# stm32_v0_7.net
KiCad netlist of a schematic drawn in EAGLE
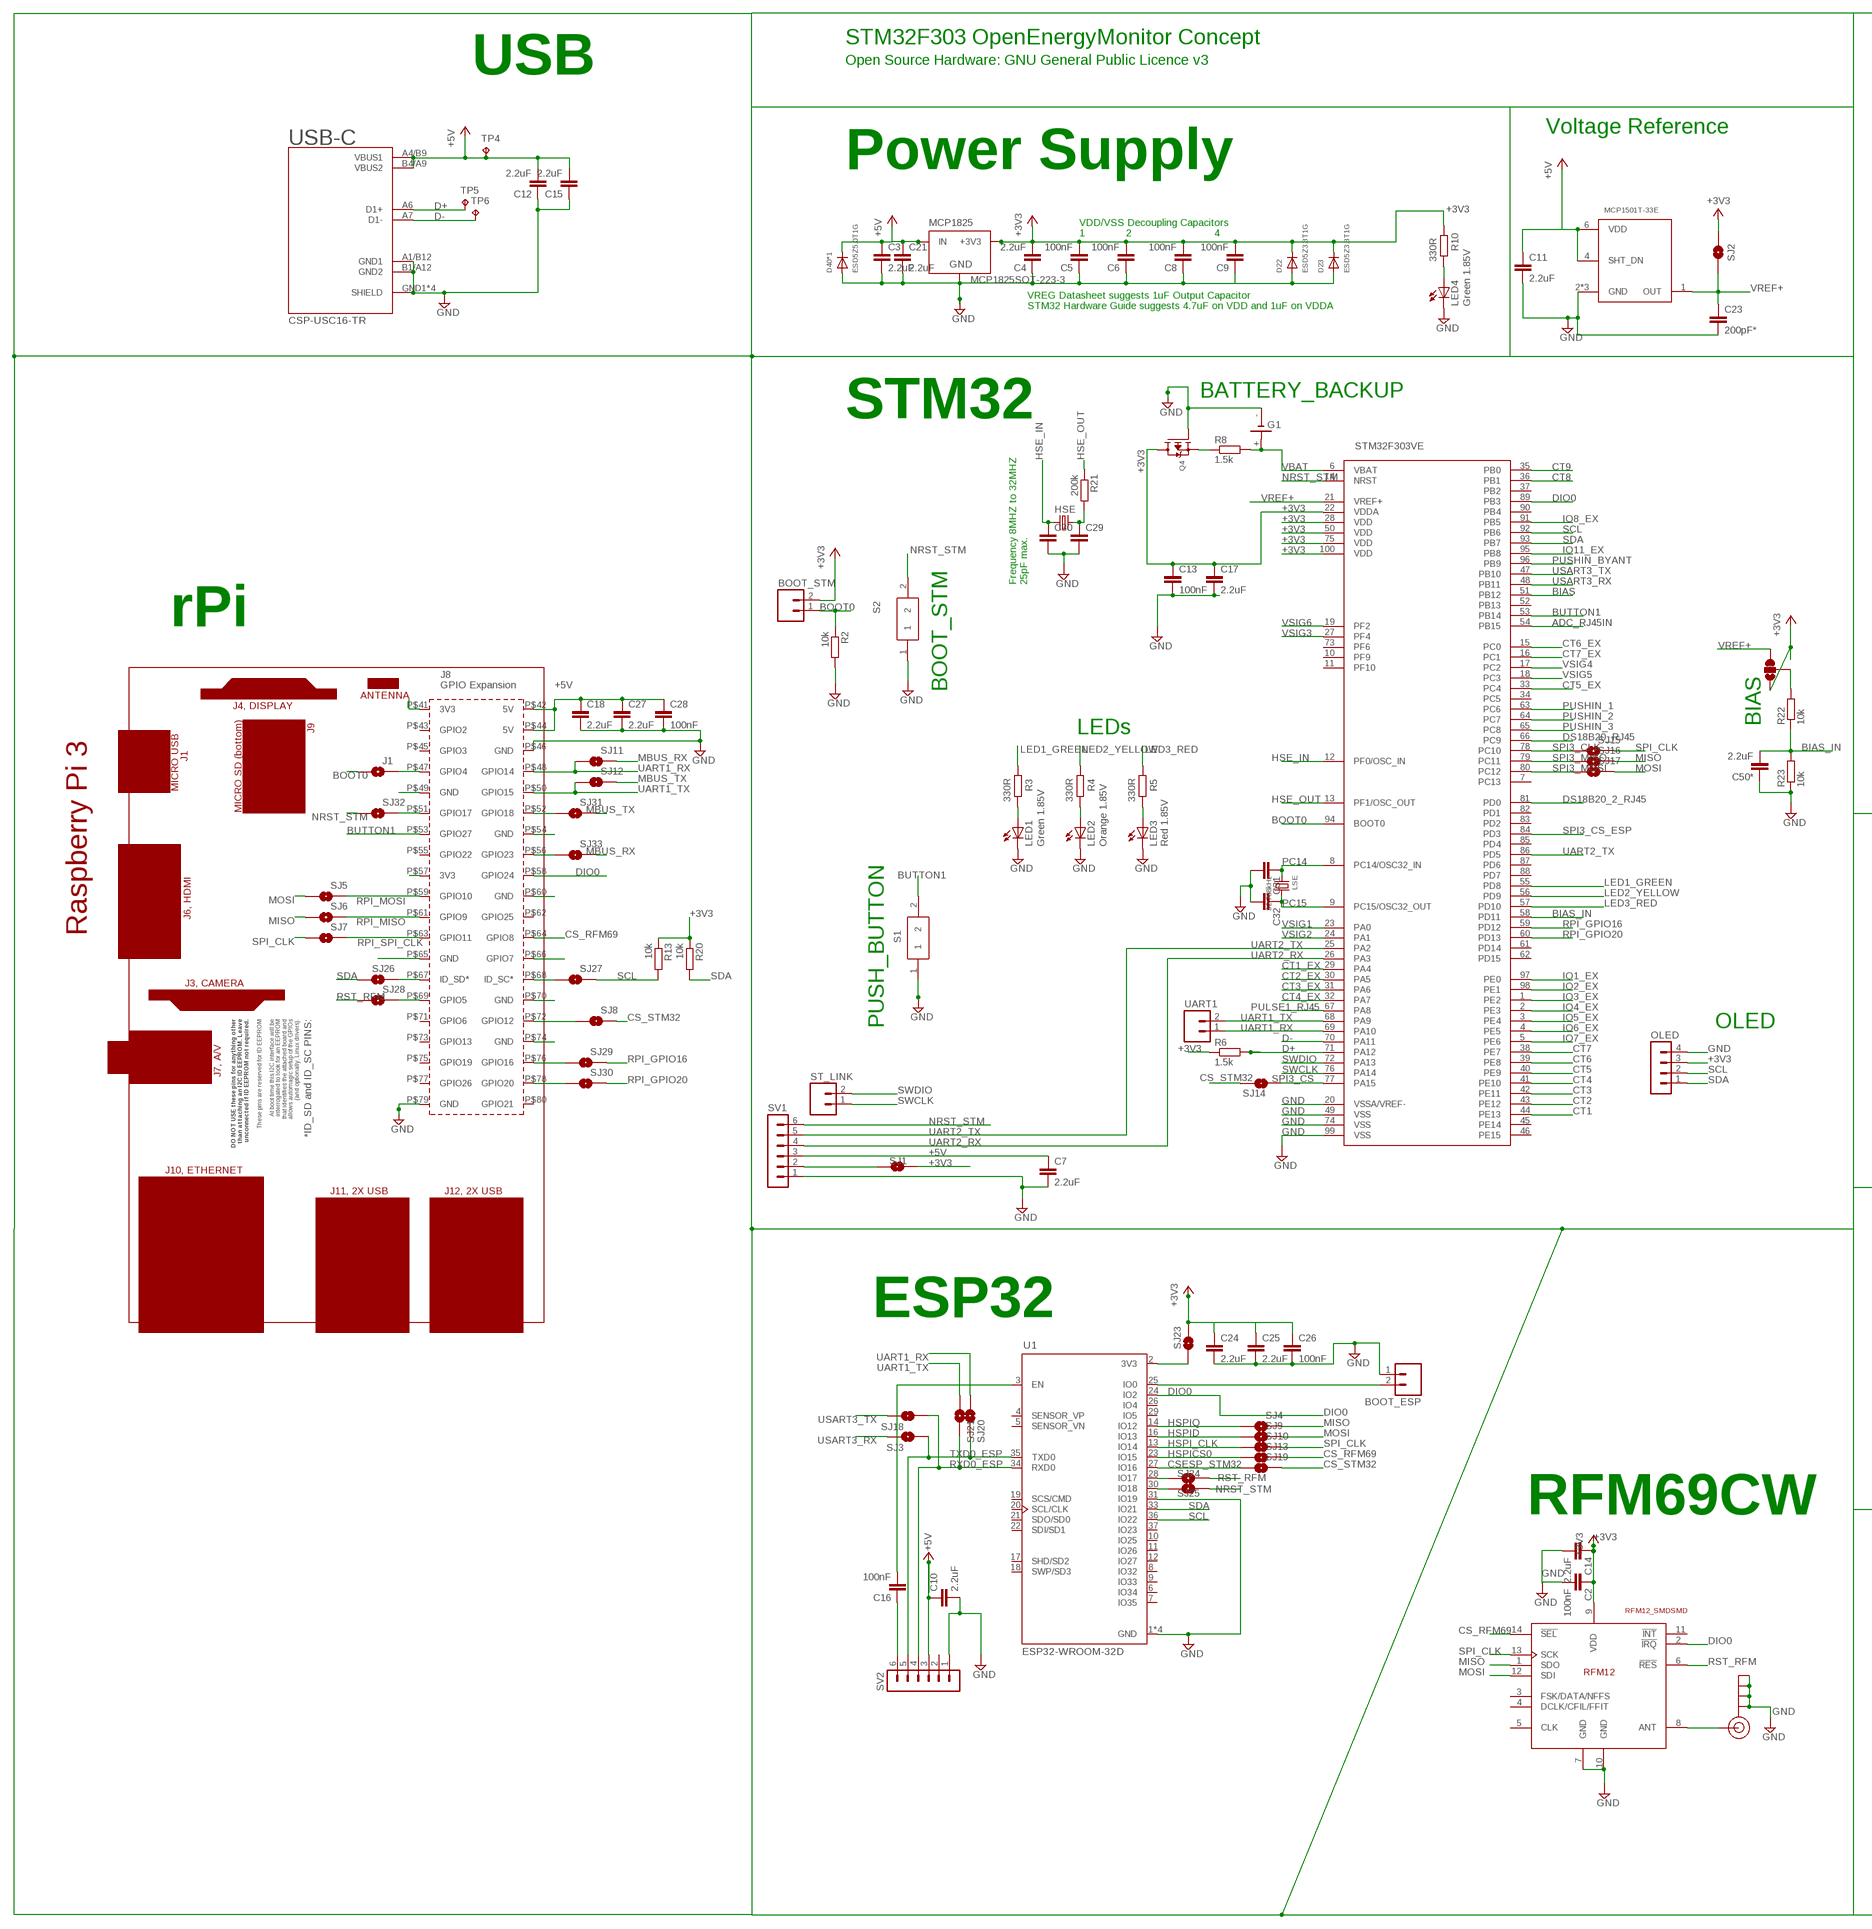
[diagram p0: schematic, sheet 1, part 1 of 2]
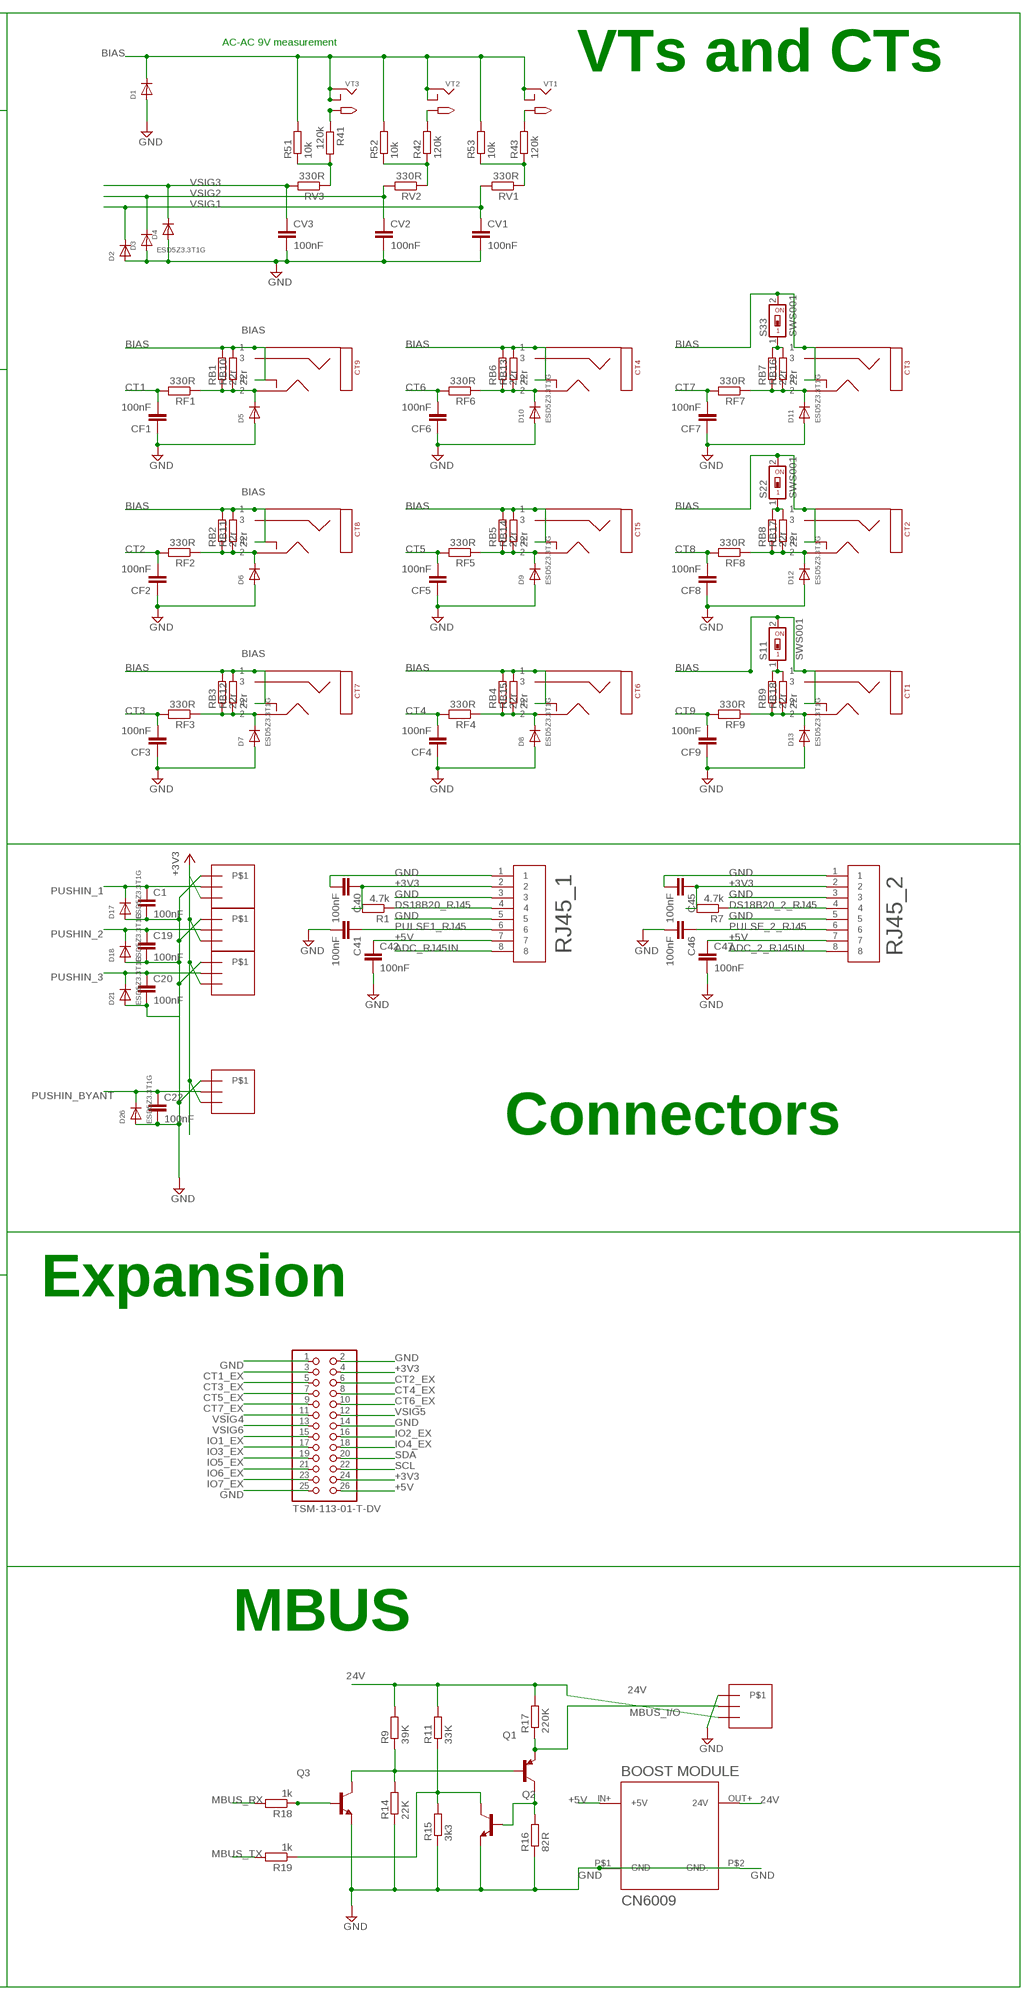
[diagram p1: schematic, sheet 1, part 2 of 2]

(export (version "E")
  (design (tool "Eeschema 10.0.6"))
  (components
    (comp (ref "BOOT_ESP")
      (value "M02PTH")
      (footprint "eagle-import:1X02")
      (libsource (lib "eagle-import") (part "M02PTH"))
    )
    (comp (ref "BOOT_STM")
      (value "M02PTH")
      (footprint "eagle-import:1X02")
      (libsource (lib "eagle-import") (part "M02PTH"))
    )
    (comp (ref "C1")
      (value "100nF")
      (footprint "eagle-import:C0603")
      (libsource (lib "eagle-import") (part "resistor_C-EUC0603"))
    )
    (comp (ref "C2")
      (value "100nF")
      (footprint "eagle-import:C0603")
      (libsource (lib "eagle-import") (part "resistor_C-EUC0603"))
    )
    (comp (ref "C3")
      (value "2.2uF")
      (footprint "eagle-import:C0805")
      (libsource (lib "eagle-import") (part "C-EUC0805"))
    )
    (comp (ref "C4")
      (value "2.2uF")
      (footprint "eagle-import:C0805")
      (libsource (lib "eagle-import") (part "C-EUC0805"))
    )
    (comp (ref "C5")
      (value "100nF")
      (footprint "eagle-import:C0603")
      (libsource (lib "eagle-import") (part "resistor_C-EUC0603"))
    )
    (comp (ref "C6")
      (value "100nF")
      (footprint "eagle-import:C0603")
      (libsource (lib "eagle-import") (part "resistor_C-EUC0603"))
    )
    (comp (ref "C7")
      (value "2.2uF")
      (footprint "eagle-import:C0805")
      (libsource (lib "eagle-import") (part "C-EUC0805"))
    )
    (comp (ref "C8")
      (value "100nF")
      (footprint "eagle-import:C0603")
      (libsource (lib "eagle-import") (part "resistor_C-EUC0603"))
    )
    (comp (ref "C9")
      (value "100nF")
      (footprint "eagle-import:C0603")
      (libsource (lib "eagle-import") (part "resistor_C-EUC0603"))
    )
    (comp (ref "C10")
      (value "2.2uF")
      (footprint "eagle-import:C0805")
      (libsource (lib "eagle-import") (part "C-EUC0805"))
    )
    (comp (ref "C11")
      (value "2.2uF")
      (footprint "eagle-import:C0805")
      (libsource (lib "eagle-import") (part "C-EUC0805"))
    )
    (comp (ref "C12")
      (value "2.2uF")
      (footprint "eagle-import:C0805")
      (libsource (lib "eagle-import") (part "C-EUC0805"))
    )
    (comp (ref "C13")
      (value "100nF")
      (footprint "eagle-import:C0603")
      (libsource (lib "eagle-import") (part "C-EUC0603"))
    )
    (comp (ref "C14")
      (value "2.2uF")
      (footprint "eagle-import:C0805")
      (libsource (lib "eagle-import") (part "C-EUC0805"))
    )
    (comp (ref "C15")
      (value "2.2uF")
      (footprint "eagle-import:C0805")
      (libsource (lib "eagle-import") (part "C-EUC0805"))
    )
    (comp (ref "C16")
      (value "100nF")
      (footprint "eagle-import:C0603")
      (libsource (lib "eagle-import") (part "resistor_C-EUC0603"))
    )
    (comp (ref "C17")
      (value "2.2uF")
      (footprint "eagle-import:C0805")
      (libsource (lib "eagle-import") (part "C-EUC0805"))
    )
    (comp (ref "C18")
      (value "2.2uF")
      (footprint "eagle-import:C0805")
      (libsource (lib "eagle-import") (part "C-EUC0805"))
    )
    (comp (ref "C19")
      (value "100nF")
      (footprint "eagle-import:C0603")
      (libsource (lib "eagle-import") (part "resistor_C-EUC0603"))
    )
    (comp (ref "C20")
      (value "100nF")
      (footprint "eagle-import:C0603")
      (libsource (lib "eagle-import") (part "resistor_C-EUC0603"))
    )
    (comp (ref "C21")
      (value "2.2uF")
      (footprint "eagle-import:C0805")
      (libsource (lib "eagle-import") (part "C-EUC0805"))
    )
    (comp (ref "C22")
      (value "100nF")
      (footprint "eagle-import:C0603")
      (libsource (lib "eagle-import") (part "resistor_C-EUC0603"))
    )
    (comp (ref "C23")
      (value "200pF*")
      (footprint "eagle-import:C0603")
      (libsource (lib "eagle-import") (part "C-EUC0603"))
    )
    (comp (ref "C24")
      (value "2.2uF")
      (footprint "eagle-import:C0805")
      (libsource (lib "eagle-import") (part "C-EUC0805"))
    )
    (comp (ref "C25")
      (value "2.2uF")
      (footprint "eagle-import:C0805")
      (libsource (lib "eagle-import") (part "C-EUC0805"))
    )
    (comp (ref "C26")
      (value "100nF")
      (footprint "eagle-import:C0603")
      (libsource (lib "eagle-import") (part "resistor_C-EUC0603"))
    )
    (comp (ref "C27")
      (value "2.2uF")
      (footprint "eagle-import:C0805")
      (libsource (lib "eagle-import") (part "C-EUC0805"))
    )
    (comp (ref "C28")
      (value "100nF")
      (footprint "eagle-import:C0603")
      (libsource (lib "eagle-import") (part "resistor_C-EUC0603"))
    )
    (comp (ref "C29")
      (value "5nF")
      (footprint "eagle-import:C0603")
      (libsource (lib "eagle-import") (part "C-EUC0603"))
    )
    (comp (ref "C30")
      (value "5nF")
      (footprint "eagle-import:C0603")
      (libsource (lib "eagle-import") (part "C-EUC0603"))
    )
    (comp (ref "C31")
      (value "2.2uF")
      (footprint "eagle-import:C0805")
      (libsource (lib "eagle-import") (part "C-EUC0805"))
    )
    (comp (ref "C32")
      (value "2.2uF")
      (footprint "eagle-import:C0805")
      (libsource (lib "eagle-import") (part "C-EUC0805"))
    )
    (comp (ref "C40")
      (value "100nF")
      (footprint "eagle-import:C0603")
      (libsource (lib "eagle-import") (part "resistor_C-EUC0603"))
    )
    (comp (ref "C41")
      (value "100nF")
      (footprint "eagle-import:C0603")
      (libsource (lib "eagle-import") (part "resistor_C-EUC0603"))
    )
    (comp (ref "C42")
      (value "100nF")
      (footprint "eagle-import:C0603")
      (libsource (lib "eagle-import") (part "resistor_C-EUC0603"))
    )
    (comp (ref "C45")
      (value "100nF")
      (footprint "eagle-import:C0603")
      (libsource (lib "eagle-import") (part "resistor_C-EUC0603"))
    )
    (comp (ref "C46")
      (value "100nF")
      (footprint "eagle-import:C0603")
      (libsource (lib "eagle-import") (part "resistor_C-EUC0603"))
    )
    (comp (ref "C47")
      (value "100nF")
      (footprint "eagle-import:C0603")
      (libsource (lib "eagle-import") (part "resistor_C-EUC0603"))
    )
    (comp (ref "C50*")
      (value "2.2uF")
      (footprint "eagle-import:C0805")
      (libsource (lib "eagle-import") (part "C-EUC0805"))
    )
    (comp (ref "CF1")
      (value "100nF")
      (footprint "eagle-import:C0603")
      (libsource (lib "eagle-import") (part "resistor_C-EUC0603"))
    )
    (comp (ref "CF2")
      (value "100nF")
      (footprint "eagle-import:C0603")
      (libsource (lib "eagle-import") (part "resistor_C-EUC0603"))
    )
    (comp (ref "CF3")
      (value "100nF")
      (footprint "eagle-import:C0603")
      (libsource (lib "eagle-import") (part "resistor_C-EUC0603"))
    )
    (comp (ref "CF4")
      (value "100nF")
      (footprint "eagle-import:C0603")
      (libsource (lib "eagle-import") (part "resistor_C-EUC0603"))
    )
    (comp (ref "CF5")
      (value "100nF")
      (footprint "eagle-import:C0603")
      (libsource (lib "eagle-import") (part "resistor_C-EUC0603"))
    )
    (comp (ref "CF6")
      (value "100nF")
      (footprint "eagle-import:C0603")
      (libsource (lib "eagle-import") (part "resistor_C-EUC0603"))
    )
    (comp (ref "CF7")
      (value "100nF")
      (footprint "eagle-import:C0603")
      (libsource (lib "eagle-import") (part "resistor_C-EUC0603"))
    )
    (comp (ref "CF8")
      (value "100nF")
      (footprint "eagle-import:C0603")
      (libsource (lib "eagle-import") (part "resistor_C-EUC0603"))
    )
    (comp (ref "CF9")
      (value "100nF")
      (footprint "eagle-import:C0603")
      (libsource (lib "eagle-import") (part "resistor_C-EUC0603"))
    )
    (comp (ref "CT1")
      (value "SJ-3523-SMT")
      (footprint "eagle-import:STEREO_SMT")
      (libsource (lib "eagle-import") (part "STEREO_SMD"))
    )
    (comp (ref "CT2")
      (value "SJ-3523-SMT")
      (footprint "eagle-import:STEREO_SMT")
      (libsource (lib "eagle-import") (part "STEREO_SMD"))
    )
    (comp (ref "CT3")
      (value "SJ-3523-SMT")
      (footprint "eagle-import:STEREO_SMT")
      (libsource (lib "eagle-import") (part "STEREO_SMD"))
    )
    (comp (ref "CT4")
      (value "SJ-3523-SMT")
      (footprint "eagle-import:STEREO_SMT")
      (libsource (lib "eagle-import") (part "STEREO_SMD"))
    )
    (comp (ref "CT5")
      (value "SJ-3523-SMT")
      (footprint "eagle-import:STEREO_SMT")
      (libsource (lib "eagle-import") (part "STEREO_SMD"))
    )
    (comp (ref "CT6")
      (value "SJ-3523-SMT")
      (footprint "eagle-import:STEREO_SMT")
      (libsource (lib "eagle-import") (part "STEREO_SMD"))
    )
    (comp (ref "CT7")
      (value "SJ-3523-SMT")
      (footprint "eagle-import:STEREO_SMT")
      (libsource (lib "eagle-import") (part "STEREO_SMD"))
    )
    (comp (ref "CT8")
      (value "SJ-3523-SMT")
      (footprint "eagle-import:STEREO_SMT")
      (libsource (lib "eagle-import") (part "STEREO_SMD"))
    )
    (comp (ref "CT9")
      (value "SJ-3523-SMT")
      (footprint "eagle-import:STEREO_SMT")
      (libsource (lib "eagle-import") (part "STEREO_SMD"))
    )
    (comp (ref "CV1")
      (value "100nF")
      (footprint "eagle-import:C0603")
      (libsource (lib "eagle-import") (part "resistor_C-EUC0603"))
    )
    (comp (ref "CV2")
      (value "100nF")
      (footprint "eagle-import:C0603")
      (libsource (lib "eagle-import") (part "resistor_C-EUC0603"))
    )
    (comp (ref "CV3")
      (value "100nF")
      (footprint "eagle-import:C0603")
      (libsource (lib "eagle-import") (part "resistor_C-EUC0603"))
    )
    (comp (ref "D1")
      (value "ESD5Z3.3T1G")
      (footprint "eagle-import:SOD-523")
      (libsource (lib "eagle-import") (part "DIODESOD-523"))
    )
    (comp (ref "D2")
      (value "ESD5Z3.3T1G")
      (footprint "eagle-import:SOD-523")
      (libsource (lib "eagle-import") (part "DIODESOD-523"))
    )
    (comp (ref "D3")
      (value "ESD5Z3.3T1G")
      (footprint "eagle-import:SOD-523")
      (libsource (lib "eagle-import") (part "DIODESOD-523"))
    )
    (comp (ref "D4")
      (value "ESD5Z3.3T1G")
      (footprint "eagle-import:SOD-523")
      (libsource (lib "eagle-import") (part "DIODESOD-523"))
    )
    (comp (ref "D5")
      (value "ESD5Z3.3T1G")
      (footprint "eagle-import:SOD-523")
      (libsource (lib "eagle-import") (part "DIODESOD-523"))
    )
    (comp (ref "D6")
      (value "ESD5Z3.3T1G")
      (footprint "eagle-import:SOD-523")
      (libsource (lib "eagle-import") (part "DIODESOD-523"))
    )
    (comp (ref "D7")
      (value "ESD5Z3.3T1G")
      (footprint "eagle-import:SOD-523")
      (libsource (lib "eagle-import") (part "DIODESOD-523"))
    )
    (comp (ref "D8")
      (value "ESD5Z3.3T1G")
      (footprint "eagle-import:SOD-523")
      (libsource (lib "eagle-import") (part "DIODESOD-523"))
    )
    (comp (ref "D9")
      (value "ESD5Z3.3T1G")
      (footprint "eagle-import:SOD-523")
      (libsource (lib "eagle-import") (part "DIODESOD-523"))
    )
    (comp (ref "D10")
      (value "ESD5Z3.3T1G")
      (footprint "eagle-import:SOD-523")
      (libsource (lib "eagle-import") (part "DIODESOD-523"))
    )
    (comp (ref "D11")
      (value "ESD5Z3.3T1G")
      (footprint "eagle-import:SOD-523")
      (libsource (lib "eagle-import") (part "DIODESOD-523"))
    )
    (comp (ref "D12")
      (value "ESD5Z3.3T1G")
      (footprint "eagle-import:SOD-523")
      (libsource (lib "eagle-import") (part "DIODESOD-523"))
    )
    (comp (ref "D13")
      (value "ESD5Z3.3T1G")
      (footprint "eagle-import:SOD-523")
      (libsource (lib "eagle-import") (part "DIODESOD-523"))
    )
    (comp (ref "D17")
      (value "ESD5Z3.3T1G")
      (footprint "eagle-import:SOD-523")
      (libsource (lib "eagle-import") (part "DIODESOD-523"))
    )
    (comp (ref "D18")
      (value "ESD5Z3.3T1G")
      (footprint "eagle-import:SOD-523")
      (libsource (lib "eagle-import") (part "DIODESOD-523"))
    )
    (comp (ref "D21")
      (value "ESD5Z3.3T1G")
      (footprint "eagle-import:SOD-523")
      (libsource (lib "eagle-import") (part "DIODESOD-523"))
    )
    (comp (ref "D22")
      (value "ESD5Z3.3T1G")
      (footprint "eagle-import:SOD-523")
      (libsource (lib "eagle-import") (part "DIODESOD-523"))
    )
    (comp (ref "D23")
      (value "ESD5Z3.3T1G")
      (footprint "eagle-import:SOD-523")
      (libsource (lib "eagle-import") (part "DIODESOD-523"))
    )
    (comp (ref "D26")
      (value "ESD5Z3.3T1G")
      (footprint "eagle-import:SOD-523")
      (libsource (lib "eagle-import") (part "DIODESOD-523"))
    )
    (comp (ref "D40*1")
      (value "ESD5Z5.0T1G")
      (footprint "eagle-import:SOD-523")
      (libsource (lib "eagle-import") (part "DIODESOD-523"))
    )
    (comp (ref "EXPANSION")
      (value "TSM-113-01-T-DV")
      (footprint "eagle-import:2X13_SMT")
      (libsource (lib "eagle-import") (part "PINHD-2X13SMT"))
    )
    (comp (ref "G1")
      (value "CH291-1220LF")
      (footprint "eagle-import:CH291-1220LF")
      (fields (field (name "MF") "Multicomp"))
      (libsource (lib "eagle-import") (part "CH291-1220LF"))
    )
    (comp (ref "HSE")
      (value "406C35E08M00000")
      (footprint "eagle-import:CTS406")
      (libsource (lib "eagle-import") (part "CRYSTALCTS406"))
    )
    (comp (ref "J$1")
      (value "SMA_EDGE")
      (footprint "eagle-import:SMA-EDGE")
      (libsource (lib "eagle-import") (part "SMA_EDGE"))
    )
    (comp (ref "J1")
      (value "SOLDERJUMPERNO")
      (footprint "eagle-import:SJ_2S-NO")
      (libsource (lib "eagle-import") (part "SOLDERJUMPERNO"))
    )
    (comp (ref "JP1")
      (value "JUMPER-SMT_3_1-NC_TRACE_NO-SILK")
      (footprint "eagle-import:SMT-JUMPER_3_1-NC_TRACE_NO-SILK")
      (libsource (lib "eagle-import") (part "JUMPER-SMT_3_1-NC_TRACE_NO-SILK"))
    )
    (comp (ref "LED1")
      (value "Green 1.85V")
      (footprint "eagle-import:CHIP-LED0805")
      (libsource (lib "eagle-import") (part "LEDCHIP-LED0805"))
    )
    (comp (ref "LED2")
      (value "Orange 1.85V")
      (footprint "eagle-import:CHIP-LED0805")
      (libsource (lib "eagle-import") (part "LEDCHIP-LED0805"))
    )
    (comp (ref "LED3")
      (value "Red 1.85V")
      (footprint "eagle-import:CHIP-LED0805")
      (libsource (lib "eagle-import") (part "LEDCHIP-LED0805"))
    )
    (comp (ref "LED4")
      (value "Green 1.85V")
      (footprint "eagle-import:CHIP-LED0805")
      (libsource (lib "eagle-import") (part "LEDCHIP-LED0805"))
    )
    (comp (ref "LSE")
      (value "32.768kHz")
      (footprint "eagle-import:CRYSTAL_8X3.8")
      (libsource (lib "eagle-import") (part "CRYSTAL8X3.8SMT"))
    )
    (comp (ref "MCP1825")
      (value "MCP1825SOT-223-3")
      (footprint "eagle-import:SOT-223")
      (libsource (lib "eagle-import") (part "MCP1825SOT-223-3"))
    )
    (comp (ref "OLED")
      (value "MA04-1-OLEDOLED")
      (footprint "eagle-import:MA04-1-OLED")
      (libsource (lib "eagle-import") (part "MA04-1-OLEDOLED"))
    )
    (comp (ref "PCB2")
      (value "TSM-120-01-T-DV")
      (footprint "eagle-import:RPI3MIRROR2")
      (libsource (lib "eagle-import") (part "RPI3YA"))
    )
    (comp (ref "Q1")
      (value "MMBT3906")
      (footprint "eagle-import:SOT23")
      (fields
        (field (name "DIGIKEY_PART_NUMBER") "MMBT3906FSCT-ND")
        (field (name "MANUFACTURER") "ON Semiconductor")
        (field (name "CREATED_BY") "PCB Layout")
      )
      (libsource (lib "eagle-import") (part "MMBT3906"))
    )
    (comp (ref "Q2")
      (value "MMBT3904")
      (footprint "eagle-import:SOT23")
      (fields
        (field (name "DIGIKEY_PART_NUMBER") "MMBT3904FSCT-ND")
        (field (name "MANUFACTURER") "ON Semiconductor")
        (field (name "CREATED_BY") "PCB Layout")
      )
      (libsource (lib "eagle-import") (part "MMBT3904"))
    )
    (comp (ref "Q3")
      (value "MMBT3904")
      (footprint "eagle-import:SOT23")
      (fields
        (field (name "DIGIKEY_PART_NUMBER") "MMBT3904FSCT-ND")
        (field (name "MANUFACTURER") "ON Semiconductor")
        (field (name "CREATED_BY") "PCB Layout")
      )
      (libsource (lib "eagle-import") (part "MMBT3904"))
    )
    (comp (ref "Q4")
      (value "MOSFET-P")
      (footprint "eagle-import:SOT23-R")
      (libsource (lib "eagle-import") (part "MOSFET-P"))
    )
    (comp (ref "R1")
      (value "4.7k")
      (footprint "eagle-import:R0603")
      (libsource (lib "eagle-import") (part "resistor_R-EU_R0603"))
    )
    (comp (ref "R2")
      (value "10k")
      (footprint "eagle-import:R0603")
      (libsource (lib "eagle-import") (part "resistor_R-EU_R0603"))
    )
    (comp (ref "R3")
      (value "330R")
      (footprint "eagle-import:R0603")
      (libsource (lib "eagle-import") (part "R-EU_R0603"))
    )
    (comp (ref "R4")
      (value "330R")
      (footprint "eagle-import:R0603")
      (libsource (lib "eagle-import") (part "R-EU_R0603"))
    )
    (comp (ref "R5")
      (value "330R")
      (footprint "eagle-import:R0603")
      (libsource (lib "eagle-import") (part "R-EU_R0603"))
    )
    (comp (ref "R6")
      (value "1.5k")
      (footprint "eagle-import:R0603")
      (libsource (lib "eagle-import") (part "R-EU_R0603"))
    )
    (comp (ref "R7")
      (value "4.7k")
      (footprint "eagle-import:R0603")
      (libsource (lib "eagle-import") (part "resistor_R-EU_R0603"))
    )
    (comp (ref "R8")
      (value "1.5k")
      (footprint "eagle-import:R0603")
      (libsource (lib "eagle-import") (part "resistor_R-EU_R0603"))
    )
    (comp (ref "R9")
      (value "39K")
      (footprint "eagle-import:R0603")
      (libsource (lib "eagle-import") (part "R-EU_R0603"))
    )
    (comp (ref "R10")
      (value "330R")
      (footprint "eagle-import:R0603")
      (libsource (lib "eagle-import") (part "R-EU_R0603"))
    )
    (comp (ref "R11")
      (value "33K")
      (footprint "eagle-import:R0603")
      (libsource (lib "eagle-import") (part "R-EU_R0603"))
    )
    (comp (ref "R13")
      (value "10k")
      (footprint "eagle-import:R0603")
      (libsource (lib "eagle-import") (part "resistor_R-EU_R0603"))
    )
    (comp (ref "R14")
      (value "22K")
      (footprint "eagle-import:R0603")
      (libsource (lib "eagle-import") (part "R-EU_R0603"))
    )
    (comp (ref "R15")
      (value "3k3")
      (footprint "eagle-import:R0603")
      (libsource (lib "eagle-import") (part "R-EU_R0603"))
    )
    (comp (ref "R16")
      (value "82R")
      (footprint "eagle-import:R0603")
      (libsource (lib "eagle-import") (part "R-EU_R0603"))
    )
    (comp (ref "R17")
      (value "220K")
      (footprint "eagle-import:R0603")
      (libsource (lib "eagle-import") (part "R-EU_R0603"))
    )
    (comp (ref "R18")
      (value "1k")
      (footprint "eagle-import:R0603")
      (libsource (lib "eagle-import") (part "R-EU_R0603"))
    )
    (comp (ref "R19")
      (value "1k")
      (footprint "eagle-import:R0603")
      (libsource (lib "eagle-import") (part "R-EU_R0603"))
    )
    (comp (ref "R20")
      (value "10k")
      (footprint "eagle-import:R0603")
      (libsource (lib "eagle-import") (part "resistor_R-EU_R0603"))
    )
    (comp (ref "R21")
      (value "200k")
      (footprint "eagle-import:R0603")
      (libsource (lib "eagle-import") (part "resistor_R-EU_R0603"))
    )
    (comp (ref "R22")
      (value "10k")
      (footprint "eagle-import:R0603")
      (libsource (lib "eagle-import") (part "resistor_R-EU_R0603"))
    )
    (comp (ref "R23")
      (value "10k")
      (footprint "eagle-import:R0603")
      (libsource (lib "eagle-import") (part "resistor_R-EU_R0603"))
    )
    (comp (ref "R41")
      (value "120k")
      (footprint "eagle-import:R0603")
      (libsource (lib "eagle-import") (part "resistor_R-EU_R0603"))
    )
    (comp (ref "R42")
      (value "120k")
      (footprint "eagle-import:R0603")
      (libsource (lib "eagle-import") (part "resistor_R-EU_R0603"))
    )
    (comp (ref "R43")
      (value "120k")
      (footprint "eagle-import:R0603")
      (libsource (lib "eagle-import") (part "resistor_R-EU_R0603"))
    )
    (comp (ref "R51")
      (value "10k")
      (footprint "eagle-import:R0603")
      (libsource (lib "eagle-import") (part "resistor_R-EU_R0603"))
    )
    (comp (ref "R52")
      (value "10k")
      (footprint "eagle-import:R0603")
      (libsource (lib "eagle-import") (part "resistor_R-EU_R0603"))
    )
    (comp (ref "R53")
      (value "10k")
      (footprint "eagle-import:R0603")
      (libsource (lib "eagle-import") (part "resistor_R-EU_R0603"))
    )
    (comp (ref "RB1")
      (value "22r")
      (footprint "eagle-import:R1206")
      (libsource (lib "eagle-import") (part "R-EU_R1206"))
    )
    (comp (ref "RB2")
      (value "22r")
      (footprint "eagle-import:R1206")
      (libsource (lib "eagle-import") (part "R-EU_R1206"))
    )
    (comp (ref "RB3")
      (value "22r")
      (footprint "eagle-import:R1206")
      (libsource (lib "eagle-import") (part "R-EU_R1206"))
    )
    (comp (ref "RB4")
      (value "22r")
      (footprint "eagle-import:R1206")
      (libsource (lib "eagle-import") (part "R-EU_R1206"))
    )
    (comp (ref "RB5")
      (value "22r")
      (footprint "eagle-import:R1206")
      (libsource (lib "eagle-import") (part "R-EU_R1206"))
    )
    (comp (ref "RB6")
      (value "22r")
      (footprint "eagle-import:R1206")
      (libsource (lib "eagle-import") (part "R-EU_R1206"))
    )
    (comp (ref "RB7")
      (value "22r")
      (footprint "eagle-import:R1206")
      (libsource (lib "eagle-import") (part "R-EU_R1206"))
    )
    (comp (ref "RB8")
      (value "22r")
      (footprint "eagle-import:R1206")
      (libsource (lib "eagle-import") (part "R-EU_R1206"))
    )
    (comp (ref "RB9")
      (value "22r")
      (footprint "eagle-import:R1206")
      (libsource (lib "eagle-import") (part "R-EU_R1206"))
    )
    (comp (ref "RB10")
      (value "22r")
      (footprint "eagle-import:0207_7")
      (libsource (lib "eagle-import") (part "R-EU_0207/7"))
    )
    (comp (ref "RB11")
      (value "22r")
      (footprint "eagle-import:0207_7")
      (libsource (lib "eagle-import") (part "R-EU_0207/7"))
    )
    (comp (ref "RB12")
      (value "22r")
      (footprint "eagle-import:0207_7")
      (libsource (lib "eagle-import") (part "R-EU_0207/7"))
    )
    (comp (ref "RB13")
      (value "22r")
      (footprint "eagle-import:0207_7")
      (libsource (lib "eagle-import") (part "R-EU_0207/7"))
    )
    (comp (ref "RB14")
      (value "22r")
      (footprint "eagle-import:0207_7")
      (libsource (lib "eagle-import") (part "R-EU_0207/7"))
    )
    (comp (ref "RB15")
      (value "22r")
      (footprint "eagle-import:0207_7")
      (libsource (lib "eagle-import") (part "R-EU_0207/7"))
    )
    (comp (ref "RB16")
      (value "22r")
      (footprint "eagle-import:0207_7")
      (libsource (lib "eagle-import") (part "R-EU_0207/7"))
    )
    (comp (ref "RB17")
      (value "22r")
      (footprint "eagle-import:0207_7")
      (libsource (lib "eagle-import") (part "R-EU_0207/7"))
    )
    (comp (ref "RB18")
      (value "22r")
      (footprint "eagle-import:0207_7")
      (libsource (lib "eagle-import") (part "R-EU_0207/7"))
    )
    (comp (ref "RF1")
      (value "330R")
      (footprint "eagle-import:R0603")
      (libsource (lib "eagle-import") (part "resistor_R-EU_R0603"))
    )
    (comp (ref "RF2")
      (value "330R")
      (footprint "eagle-import:R0603")
      (libsource (lib "eagle-import") (part "resistor_R-EU_R0603"))
    )
    (comp (ref "RF3")
      (value "330R")
      (footprint "eagle-import:R0603")
      (libsource (lib "eagle-import") (part "resistor_R-EU_R0603"))
    )
    (comp (ref "RF4")
      (value "330R")
      (footprint "eagle-import:R0603")
      (libsource (lib "eagle-import") (part "resistor_R-EU_R0603"))
    )
    (comp (ref "RF5")
      (value "330R")
      (footprint "eagle-import:R0603")
      (libsource (lib "eagle-import") (part "resistor_R-EU_R0603"))
    )
    (comp (ref "RF6")
      (value "330R")
      (footprint "eagle-import:R0603")
      (libsource (lib "eagle-import") (part "resistor_R-EU_R0603"))
    )
    (comp (ref "RF7")
      (value "330R")
      (footprint "eagle-import:R0603")
      (libsource (lib "eagle-import") (part "resistor_R-EU_R0603"))
    )
    (comp (ref "RF8")
      (value "330R")
      (footprint "eagle-import:R0603")
      (libsource (lib "eagle-import") (part "resistor_R-EU_R0603"))
    )
    (comp (ref "RF9")
      (value "330R")
      (footprint "eagle-import:R0603")
      (libsource (lib "eagle-import") (part "resistor_R-EU_R0603"))
    )
    (comp (ref "RFM69HCW")
      (value "RFM12_SMDSMD")
      (footprint "eagle-import:RFM12")
      (libsource (lib "eagle-import") (part "RFM12_SMDSMD"))
    )
    (comp (ref "RJ45_1")
      (value "95501-6889")
      (footprint "eagle-import:955016889")
      (fields (field (name "MOUSER_PART_NUMBER") "538-95501-6889") (field (name "RS_PART_NUMBER") "3862738"))
      (libsource (lib "eagle-import") (part "95501-6889"))
    )
    (comp (ref "RJ45_2")
      (value "95501-6889")
      (footprint "eagle-import:955016889")
      (fields (field (name "MOUSER_PART_NUMBER") "538-95501-6889") (field (name "RS_PART_NUMBER") "3862738"))
      (libsource (lib "eagle-import") (part "95501-6889"))
    )
    (comp (ref "RV1")
      (value "330R")
      (footprint "eagle-import:R0603")
      (libsource (lib "eagle-import") (part "resistor_R-EU_R0603"))
    )
    (comp (ref "RV2")
      (value "330R")
      (footprint "eagle-import:R0603")
      (libsource (lib "eagle-import") (part "resistor_R-EU_R0603"))
    )
    (comp (ref "RV3")
      (value "330R")
      (footprint "eagle-import:R0603")
      (libsource (lib "eagle-import") (part "resistor_R-EU_R0603"))
    )
    (comp (ref "S1")
      (value "KSS221GLFS")
      (footprint "eagle-import:KSS")
      (fields (field (name "RS_PART_NUMBER") "7931689P"))
      (libsource (lib "eagle-import") (part "KSS221GLFS"))
    )
    (comp (ref "S2")
      (value "KSS221GLFS")
      (footprint "eagle-import:KSS")
      (fields (field (name "RS_PART_NUMBER") "7931689P"))
      (libsource (lib "eagle-import") (part "KSS221GLFS"))
    )
    (comp (ref "S11")
      (value "SWS001")
      (footprint "eagle-import:SMS-001")
      (libsource (lib "eagle-import") (part "SWS001"))
    )
    (comp (ref "S22")
      (value "SWS001")
      (footprint "eagle-import:SMS-001")
      (libsource (lib "eagle-import") (part "SWS001"))
    )
    (comp (ref "S33")
      (value "SWS001")
      (footprint "eagle-import:SMS-001")
      (libsource (lib "eagle-import") (part "SWS001"))
    )
    (comp (ref "SJ1")
      (value "SOLDERJUMPERNO")
      (footprint "eagle-import:SJ_2S-NO")
      (libsource (lib "eagle-import") (part "SOLDERJUMPERNO"))
    )
    (comp (ref "SJ2")
      (value "SOLDERJUMPERNO")
      (footprint "eagle-import:SJ_2S-NO")
      (libsource (lib "eagle-import") (part "SOLDERJUMPERNO"))
    )
    (comp (ref "SJ3")
      (value "SOLDERJUMPERNO")
      (footprint "eagle-import:SJ_2S-NO")
      (libsource (lib "eagle-import") (part "SOLDERJUMPERNO"))
    )
    (comp (ref "SJ4")
      (value "SOLDERJUMPERNO")
      (footprint "eagle-import:SJ_2S-NO")
      (libsource (lib "eagle-import") (part "SOLDERJUMPERNO"))
    )
    (comp (ref "SJ5")
      (value "SOLDERJUMPERNO")
      (footprint "eagle-import:SJ_2S-NO")
      (libsource (lib "eagle-import") (part "SOLDERJUMPERNO"))
    )
    (comp (ref "SJ6")
      (value "SOLDERJUMPERNO")
      (footprint "eagle-import:SJ_2S-NO")
      (libsource (lib "eagle-import") (part "SOLDERJUMPERNO"))
    )
    (comp (ref "SJ7")
      (value "SOLDERJUMPERNO")
      (footprint "eagle-import:SJ_2S-NO")
      (libsource (lib "eagle-import") (part "SOLDERJUMPERNO"))
    )
    (comp (ref "SJ8")
      (value "SOLDERJUMPERNO")
      (footprint "eagle-import:SJ_2S-NO")
      (libsource (lib "eagle-import") (part "SOLDERJUMPERNO"))
    )
    (comp (ref "SJ9")
      (value "SOLDERJUMPERNO")
      (footprint "eagle-import:SJ_2S-NO")
      (libsource (lib "eagle-import") (part "SOLDERJUMPERNO"))
    )
    (comp (ref "SJ10")
      (value "SOLDERJUMPERNO")
      (footprint "eagle-import:SJ_2S-NO")
      (libsource (lib "eagle-import") (part "SOLDERJUMPERNO"))
    )
    (comp (ref "SJ11")
      (value "SOLDERJUMPERNO")
      (footprint "eagle-import:SJ_2S-NO")
      (libsource (lib "eagle-import") (part "SOLDERJUMPERNO"))
    )
    (comp (ref "SJ12")
      (value "SOLDERJUMPERNO")
      (footprint "eagle-import:SJ_2S-NO")
      (libsource (lib "eagle-import") (part "SOLDERJUMPERNO"))
    )
    (comp (ref "SJ13")
      (value "SOLDERJUMPERNO")
      (footprint "eagle-import:SJ_2S-NO")
      (libsource (lib "eagle-import") (part "SOLDERJUMPERNO"))
    )
    (comp (ref "SJ14")
      (value "SOLDERJUMPERNO")
      (footprint "eagle-import:SJ_2S-NO")
      (libsource (lib "eagle-import") (part "SOLDERJUMPERNO"))
    )
    (comp (ref "SJ15")
      (value "SOLDERJUMPERNO")
      (footprint "eagle-import:SJ_2S-NO")
      (libsource (lib "eagle-import") (part "SOLDERJUMPERNO"))
    )
    (comp (ref "SJ16")
      (value "SOLDERJUMPERNO")
      (footprint "eagle-import:SJ_2S-NO")
      (libsource (lib "eagle-import") (part "SOLDERJUMPERNO"))
    )
    (comp (ref "SJ17")
      (value "SOLDERJUMPERNO")
      (footprint "eagle-import:SJ_2S-NO")
      (libsource (lib "eagle-import") (part "SOLDERJUMPERNO"))
    )
    (comp (ref "SJ18")
      (value "SOLDERJUMPERNO")
      (footprint "eagle-import:SJ_2S-NO")
      (libsource (lib "eagle-import") (part "SOLDERJUMPERNO"))
    )
    (comp (ref "SJ19")
      (value "SOLDERJUMPERNO")
      (footprint "eagle-import:SJ_2S-NO")
      (libsource (lib "eagle-import") (part "SOLDERJUMPERNO"))
    )
    (comp (ref "SJ20")
      (value "SOLDERJUMPERNO")
      (footprint "eagle-import:SJ_2S-NO")
      (libsource (lib "eagle-import") (part "SOLDERJUMPERNO"))
    )
    (comp (ref "SJ21")
      (value "SOLDERJUMPERNO")
      (footprint "eagle-import:SJ_2S-NO")
      (libsource (lib "eagle-import") (part "SOLDERJUMPERNO"))
    )
    (comp (ref "SJ23")
      (value "SOLDERJUMPERNO")
      (footprint "eagle-import:SJ_2S-NO")
      (libsource (lib "eagle-import") (part "SOLDERJUMPERNO"))
    )
    (comp (ref "SJ24")
      (value "SOLDERJUMPERNO")
      (footprint "eagle-import:SJ_2S-NO")
      (libsource (lib "eagle-import") (part "SOLDERJUMPERNO"))
    )
    (comp (ref "SJ25")
      (value "SOLDERJUMPERNO")
      (footprint "eagle-import:SJ_2S-NO")
      (libsource (lib "eagle-import") (part "SOLDERJUMPERNO"))
    )
    (comp (ref "SJ26")
      (value "SOLDERJUMPERNO")
      (footprint "eagle-import:SJ_2S-NO")
      (libsource (lib "eagle-import") (part "SOLDERJUMPERNO"))
    )
    (comp (ref "SJ27")
      (value "SOLDERJUMPERNO")
      (footprint "eagle-import:SJ_2S-NO")
      (libsource (lib "eagle-import") (part "SOLDERJUMPERNO"))
    )
    (comp (ref "SJ28")
      (value "SOLDERJUMPERNO")
      (footprint "eagle-import:SJ_2S-NO")
      (libsource (lib "eagle-import") (part "SOLDERJUMPERNO"))
    )
    (comp (ref "SJ29")
      (value "SOLDERJUMPERNO")
      (footprint "eagle-import:SJ_2S-NO")
      (libsource (lib "eagle-import") (part "SOLDERJUMPERNO"))
    )
    (comp (ref "SJ30")
      (value "SOLDERJUMPERNO")
      (footprint "eagle-import:SJ_2S-NO")
      (libsource (lib "eagle-import") (part "SOLDERJUMPERNO"))
    )
    (comp (ref "SJ31")
      (value "SOLDERJUMPERNO")
      (footprint "eagle-import:SJ_2S-NO")
      (libsource (lib "eagle-import") (part "SOLDERJUMPERNO"))
    )
    (comp (ref "SJ32")
      (value "SOLDERJUMPERNO")
      (footprint "eagle-import:SJ_2S-NO")
      (libsource (lib "eagle-import") (part "SOLDERJUMPERNO"))
    )
    (comp (ref "SJ33")
      (value "SOLDERJUMPERNO")
      (footprint "eagle-import:SJ_2S-NO")
      (libsource (lib "eagle-import") (part "SOLDERJUMPERNO"))
    )
    (comp (ref "STM32F303VE")
      (value "STM32F303VE")
      (footprint "eagle-import:TQFP100")
      (libsource (lib "eagle-import") (part "STM32F303XB"))
    )
    (comp (ref "ST_LINK")
      (value "M02PTH")
      (footprint "eagle-import:1X02")
      (libsource (lib "eagle-import") (part "M02PTH"))
    )
    (comp (ref "SV1")
      (value "MA06-1")
      (footprint "eagle-import:MA06-1")
      (libsource (lib "eagle-import") (part "MA06-1"))
    )
    (comp (ref "SV2")
      (value "MA06-1")
      (footprint "eagle-import:MA06-1")
      (libsource (lib "eagle-import") (part "MA06-1"))
    )
    (comp (ref "TP4")
      (value "TPB1,27")
      (footprint "eagle-import:B1,27")
      (libsource (lib "eagle-import") (part "TPB1,27"))
    )
    (comp (ref "TP5")
      (value "TPB1,27")
      (footprint "eagle-import:B1,27")
      (libsource (lib "eagle-import") (part "TPB1,27"))
    )
    (comp (ref "TP6")
      (value "TPB1,27")
      (footprint "eagle-import:B1,27")
      (libsource (lib "eagle-import") (part "TPB1,27"))
    )
    (comp (ref "U$1")
      (value "3.5MM_TERMINAL_BLOCK")
      (footprint "eagle-import:3.5MM_X3")
      (fields (field (name "MPN") "144-4326"))
      (libsource (lib "eagle-import") (part "3.5MM_TERMINAL_BLOCK"))
    )
    (comp (ref "U$2")
      (value "BOOST_MODULE")
      (footprint "eagle-import:BOOST")
      (libsource (lib "eagle-import") (part "BOOST_MODULE"))
    )
    (comp (ref "U$3")
      (value "3.5MM_TERMINAL_BLOCK")
      (footprint "eagle-import:3.5MM_X3")
      (fields (field (name "MPN") "144-4326"))
      (libsource (lib "eagle-import") (part "3.5MM_TERMINAL_BLOCK"))
    )
    (comp (ref "U$4")
      (value "3.5MM_TERMINAL_BLOCK")
      (footprint "eagle-import:3.5MM_X3")
      (fields (field (name "MPN") "144-4326"))
      (libsource (lib "eagle-import") (part "3.5MM_TERMINAL_BLOCK"))
    )
    (comp (ref "U$5")
      (value "3.5MM_TERMINAL_BLOCK")
      (footprint "eagle-import:3.5MM_X3")
      (fields (field (name "MPN") "144-4326"))
      (libsource (lib "eagle-import") (part "3.5MM_TERMINAL_BLOCK"))
    )
    (comp (ref "U$6")
      (value "3.5MM_TERMINAL_BLOCK")
      (footprint "eagle-import:3.5MM_X3")
      (fields (field (name "MPN") "144-4326"))
      (libsource (lib "eagle-import") (part "3.5MM_TERMINAL_BLOCK"))
    )
    (comp (ref "U1")
      (value "ESP32-WROOM-32D")
      (footprint "eagle-import:MODULE_ESP32-WROOM-32D")
      (fields (field (name "MF") "Espressif Systems"))
      (libsource (lib "eagle-import") (part "ESP32-WROOM-32D"))
    )
    (comp (ref "UART1")
      (value "M02PTH")
      (footprint "eagle-import:1X02")
      (libsource (lib "eagle-import") (part "M02PTH"))
    )
    (comp (ref "USB-C")
      (value "CSP-USC16-TR")
      (footprint "eagle-import:USB-C")
      (libsource (lib "eagle-import") (part "CSP-USC16-TR"))
    )
    (comp (ref "VREF_3V3")
      (value "MCP1501T-33E")
      (footprint "eagle-import:SOT95P280X145-6N")
      (libsource (lib "eagle-import") (part "MCP1501T-33E"))
    )
    (comp (ref "VT1")
      (value "ADC-028-2-T")
      (footprint "eagle-import:DCJACK_2MM_SMT")
      (fields (field (name "MPN") "ADC-028-1-T"))
      (libsource (lib "eagle-import") (part "2.1MMJACKSMT"))
    )
    (comp (ref "VT2")
      (value "ADC-028-2-T")
      (footprint "eagle-import:DCJACK_2MM_SMT")
      (fields (field (name "MPN") "ADC-028-1-T"))
      (libsource (lib "eagle-import") (part "2.1MMJACKSMT"))
    )
    (comp (ref "VT3")
      (value "ADC-028-2-T")
      (footprint "eagle-import:DCJACK_2MM_SMT")
      (fields (field (name "MPN") "ADC-028-1-T"))
      (libsource (lib "eagle-import") (part "2.1MMJACKSMT"))
    )
  )
  (nets
    (net (code "1") (name "+3V3") (class "Default")
      (node (ref "BOOT_STM") (pin "2") (pinfunction "2_2") (pintype "passive"))
      (node (ref "C13") (pin "1") (pinfunction "1_1") (pintype "passive"))
      (node (ref "C14") (pin "1") (pinfunction "1_1") (pintype "passive"))
      (node (ref "C17") (pin "1") (pinfunction "1_1") (pintype "passive"))
      (node (ref "C2") (pin "1") (pinfunction "1_1") (pintype "passive"))
      (node (ref "C24") (pin "1") (pinfunction "1_1") (pintype "passive"))
      (node (ref "C25") (pin "1") (pinfunction "1_1") (pintype "passive"))
      (node (ref "C26") (pin "1") (pinfunction "1_1") (pintype "passive"))
      (node (ref "C4") (pin "2") (pinfunction "2_2") (pintype "passive"))
      (node (ref "C40") (pin "1") (pinfunction "1_1") (pintype "passive"))
      (node (ref "C45") (pin "1") (pinfunction "1_1") (pintype "passive"))
      (node (ref "C5") (pin "2") (pinfunction "2_2") (pintype "passive"))
      (node (ref "C6") (pin "2") (pinfunction "2_2") (pintype "passive"))
      (node (ref "C8") (pin "2") (pinfunction "2_2") (pintype "passive"))
      (node (ref "C9") (pin "2") (pinfunction "2_2") (pintype "passive"))
      (node (ref "D22") (pin "K") (pinfunction "C_K") (pintype "passive"))
      (node (ref "D23") (pin "K") (pinfunction "C_K") (pintype "passive"))
      (node (ref "EXPANSION") (pin "24") (pinfunction "24_24") (pintype "passive"))
      (node (ref "EXPANSION") (pin "4") (pinfunction "4_4") (pintype "passive"))
      (node (ref "JP1") (pin "1") (pinfunction "1_1") (pintype "passive"))
      (node (ref "MCP1825") (pin "3") (pinfunction "+3V3_3") (pintype "power_in"))
      (node (ref "OLED") (pin "3") (pinfunction "3_3") (pintype "passive"))
      (node (ref "Q4") (pin "3") (pinfunction "D_3") (pintype "passive"))
      (node (ref "R1") (pin "2") (pinfunction "2_2") (pintype "passive"))
      (node (ref "R10") (pin "2") (pinfunction "2_2") (pintype "passive"))
      (node (ref "R13") (pin "1") (pinfunction "1_1") (pintype "passive"))
      (node (ref "R20") (pin "1") (pinfunction "1_1") (pintype "passive"))
      (node (ref "R6") (pin "1") (pinfunction "1_1") (pintype "passive"))
      (node (ref "R7") (pin "2") (pinfunction "2_2") (pintype "passive"))
      (node (ref "RFM69HCW") (pin "9") (pinfunction "VDD_9") (pintype "power_in"))
      (node (ref "RJ45_1") (pin "2") (pinfunction "2_2") (pintype "bidirectional"))
      (node (ref "RJ45_2") (pin "2") (pinfunction "2_2") (pintype "bidirectional"))
      (node (ref "SJ1") (pin "2") (pinfunction "2_2") (pintype "passive"))
      (node (ref "SJ2") (pin "1") (pinfunction "1_1") (pintype "passive"))
      (node (ref "SJ23") (pin "2") (pinfunction "2_2") (pintype "passive"))
      (node (ref "STM32F303VE") (pin "100") (pinfunction "VDD_100") (pintype "bidirectional"))
      (node (ref "STM32F303VE") (pin "22") (pinfunction "VDDA_22") (pintype "bidirectional"))
      (node (ref "STM32F303VE") (pin "28") (pinfunction "VDD_28") (pintype "bidirectional"))
      (node (ref "STM32F303VE") (pin "50") (pinfunction "VDD_50") (pintype "bidirectional"))
      (node (ref "STM32F303VE") (pin "75") (pinfunction "VDD_75") (pintype "bidirectional"))
      (node (ref "U$1") (pin "P$1") (pinfunction "P$3_P$1") (pintype "bidirectional"))
      (node (ref "U$3") (pin "P$1") (pinfunction "P$3_P$1") (pintype "bidirectional"))
      (node (ref "U$4") (pin "P$1") (pinfunction "P$3_P$1") (pintype "bidirectional"))
      (node (ref "U$5") (pin "P$1") (pinfunction "P$3_P$1") (pintype "bidirectional"))
    )
    (net (code "2") (name "+5V") (class "Default")
      (node (ref "C10") (pin "1") (pinfunction "1_1") (pintype "passive"))
      (node (ref "C11") (pin "1") (pinfunction "1_1") (pintype "passive"))
      (node (ref "C12") (pin "2") (pinfunction "2_2") (pintype "passive"))
      (node (ref "C15") (pin "2") (pinfunction "2_2") (pintype "passive"))
      (node (ref "C18") (pin "1") (pinfunction "1_1") (pintype "passive"))
      (node (ref "C21") (pin "1") (pinfunction "1_1") (pintype "passive"))
      (node (ref "C27") (pin "1") (pinfunction "1_1") (pintype "passive"))
      (node (ref "C28") (pin "1") (pinfunction "1_1") (pintype "passive"))
      (node (ref "C3") (pin "1") (pinfunction "1_1") (pintype "passive"))
      (node (ref "C42") (pin "1") (pinfunction "1_1") (pintype "passive"))
      (node (ref "C47") (pin "1") (pinfunction "1_1") (pintype "passive"))
      (node (ref "C7") (pin "1") (pinfunction "1_1") (pintype "passive"))
      (node (ref "D40*1") (pin "K") (pinfunction "C_K") (pintype "passive"))
      (node (ref "EXPANSION") (pin "26") (pinfunction "26_26") (pintype "passive"))
      (node (ref "MCP1825") (pin "1") (pinfunction "IN_1") (pintype "power_in"))
      (node (ref "PCB2") (pin "P$42") (pinfunction "5V_P$42") (pintype "bidirectional"))
      (node (ref "PCB2") (pin "P$44") (pinfunction "5V_P$44") (pintype "bidirectional"))
      (node (ref "RJ45_1") (pin "7") (pinfunction "7_7") (pintype "bidirectional"))
      (node (ref "RJ45_2") (pin "7") (pinfunction "7_7") (pintype "bidirectional"))
      (node (ref "SV1") (pin "3") (pinfunction "3_3") (pintype "passive"))
      (node (ref "SV2") (pin "3") (pinfunction "3_3") (pintype "passive"))
      (node (ref "TP4") (pin "TP") (pinfunction "TP_TP") (pintype "input"))
      (node (ref "U$2") (pin "IN+") (pinfunction "+5V_IN+") (pintype "bidirectional"))
      (node (ref "USB-C") (pin "A4/B9") (pinfunction "VBUS1_A4/B9") (pintype "passive"))
      (node (ref "USB-C") (pin "B4/A9") (pinfunction "VBUS2_B4/A9") (pintype "passive"))
      (node (ref "VREF_3V3") (pin "4") (pinfunction "SHT_DN_4") (pintype "bidirectional"))
      (node (ref "VREF_3V3") (pin "6") (pinfunction "VDD_6") (pintype "bidirectional"))
    )
    (net (code "3") (name "/24V") (class "Default")
      (node (ref "R11") (pin "2") (pinfunction "2_2") (pintype "passive"))
      (node (ref "R17") (pin "2") (pinfunction "2_2") (pintype "passive"))
      (node (ref "R9") (pin "2") (pinfunction "2_2") (pintype "passive"))
      (node (ref "U$2") (pin "OUT+") (pinfunction "24V_OUT+") (pintype "bidirectional"))
      (node (ref "U$6") (pin "P$1") (pinfunction "P$3_P$1") (pintype "bidirectional"))
    )
    (net (code "4") (name "/ADC_2_RJ45IN") (class "Default")
      (node (ref "RJ45_2") (pin "8") (pinfunction "8_8") (pintype "bidirectional"))
    )
    (net (code "5") (name "/ADC_RJ45IN") (class "Default")
      (node (ref "RJ45_1") (pin "8") (pinfunction "8_8") (pintype "bidirectional"))
      (node (ref "STM32F303VE") (pin "54") (pinfunction "PB15_54") (pintype "bidirectional"))
    )
    (net (code "6") (name "/BIAS") (class "Default")
      (node (ref "CT1") (pin "P$1") (pinfunction "1_P$1") (pintype "bidirectional"))
      (node (ref "CT1") (pin "P$4") (pinfunction "4_P$4") (pintype "bidirectional"))
      (node (ref "CT2") (pin "P$1") (pinfunction "1_P$1") (pintype "bidirectional"))
      (node (ref "CT2") (pin "P$4") (pinfunction "4_P$4") (pintype "bidirectional"))
      (node (ref "CT3") (pin "P$1") (pinfunction "1_P$1") (pintype "bidirectional"))
      (node (ref "CT3") (pin "P$4") (pinfunction "4_P$4") (pintype "bidirectional"))
      (node (ref "CT4") (pin "P$1") (pinfunction "1_P$1") (pintype "bidirectional"))
      (node (ref "CT4") (pin "P$4") (pinfunction "4_P$4") (pintype "bidirectional"))
      (node (ref "CT5") (pin "P$1") (pinfunction "1_P$1") (pintype "bidirectional"))
      (node (ref "CT5") (pin "P$4") (pinfunction "4_P$4") (pintype "bidirectional"))
      (node (ref "CT6") (pin "P$1") (pinfunction "1_P$1") (pintype "bidirectional"))
      (node (ref "CT6") (pin "P$4") (pinfunction "4_P$4") (pintype "bidirectional"))
      (node (ref "CT7") (pin "P$1") (pinfunction "1_P$1") (pintype "bidirectional"))
      (node (ref "CT7") (pin "P$4") (pinfunction "4_P$4") (pintype "bidirectional"))
      (node (ref "CT8") (pin "P$1") (pinfunction "1_P$1") (pintype "bidirectional"))
      (node (ref "CT8") (pin "P$4") (pinfunction "4_P$4") (pintype "bidirectional"))
      (node (ref "CT9") (pin "P$1") (pinfunction "1_P$1") (pintype "bidirectional"))
      (node (ref "CT9") (pin "P$4") (pinfunction "4_P$4") (pintype "bidirectional"))
      (node (ref "D1") (pin "K") (pinfunction "C_K") (pintype "passive"))
      (node (ref "R51") (pin "2") (pinfunction "2_2") (pintype "passive"))
      (node (ref "R52") (pin "2") (pinfunction "2_2") (pintype "passive"))
      (node (ref "R53") (pin "2") (pinfunction "2_2") (pintype "passive"))
      (node (ref "RB1") (pin "2") (pinfunction "2_2") (pintype "passive"))
      (node (ref "RB10") (pin "2") (pinfunction "2_2") (pintype "passive"))
      (node (ref "RB11") (pin "2") (pinfunction "2_2") (pintype "passive"))
      (node (ref "RB12") (pin "2") (pinfunction "2_2") (pintype "passive"))
      (node (ref "RB13") (pin "2") (pinfunction "2_2") (pintype "passive"))
      (node (ref "RB14") (pin "2") (pinfunction "2_2") (pintype "passive"))
      (node (ref "RB15") (pin "2") (pinfunction "2_2") (pintype "passive"))
      (node (ref "RB2") (pin "2") (pinfunction "2_2") (pintype "passive"))
      (node (ref "RB3") (pin "2") (pinfunction "2_2") (pintype "passive"))
      (node (ref "RB4") (pin "2") (pinfunction "2_2") (pintype "passive"))
      (node (ref "RB5") (pin "2") (pinfunction "2_2") (pintype "passive"))
      (node (ref "RB6") (pin "2") (pinfunction "2_2") (pintype "passive"))
      (node (ref "S11") (pin "2") (pinfunction "2_2") (pintype "passive"))
      (node (ref "S22") (pin "2") (pinfunction "2_2") (pintype "passive"))
      (node (ref "S33") (pin "2") (pinfunction "2_2") (pintype "passive"))
      (node (ref "STM32F303VE") (pin "51") (pinfunction "PB12_51") (pintype "bidirectional"))
      (node (ref "VT1") (pin "GND") (pinfunction "RING_GND") (pintype "bidirectional"))
      (node (ref "VT1") (pin "GNDBREAK") (pinfunction "RING_SW_GNDBREAK") (pintype "bidirectional"))
      (node (ref "VT2") (pin "GND") (pinfunction "RING_GND") (pintype "bidirectional"))
      (node (ref "VT2") (pin "GNDBREAK") (pinfunction "RING_SW_GNDBREAK") (pintype "bidirectional"))
      (node (ref "VT3") (pin "GND") (pinfunction "RING_GND") (pintype "bidirectional"))
      (node (ref "VT3") (pin "GNDBREAK") (pinfunction "RING_SW_GNDBREAK") (pintype "bidirectional"))
    )
    (net (code "7") (name "/BIAS_IN") (class "Default")
      (node (ref "C50*") (pin "2") (pinfunction "2_2") (pintype "passive"))
      (node (ref "R22") (pin "1") (pinfunction "1_1") (pintype "passive"))
      (node (ref "R23") (pin "2") (pinfunction "2_2") (pintype "passive"))
      (node (ref "STM32F303VE") (pin "58") (pinfunction "PD11_58") (pintype "bidirectional"))
    )
    (net (code "8") (name "/BOOT0") (class "Default")
      (node (ref "BOOT_STM") (pin "1") (pinfunction "1_1") (pintype "passive"))
      (node (ref "J1") (pin "1") (pinfunction "1_1") (pintype "passive"))
      (node (ref "R2") (pin "1") (pinfunction "1_1") (pintype "passive"))
      (node (ref "STM32F303VE") (pin "94") (pinfunction "BOOT0_94") (pintype "bidirectional"))
    )
    (net (code "9") (name "/BUTTON1") (class "Default")
      (node (ref "PCB2") (pin "P$53") (pinfunction "GPIO27_P$53") (pintype "bidirectional"))
      (node (ref "S1") (pin "2") (pinfunction "2_2") (pintype "bidirectional"))
      (node (ref "STM32F303VE") (pin "53") (pinfunction "PB14_53") (pintype "bidirectional"))
    )
    (net (code "10") (name "/CSESP_STM32") (class "Default")
      (node (ref "SJ19") (pin "1") (pinfunction "1_1") (pintype "passive"))
      (node (ref "U1") (pin "27") (pinfunction "IO16_27") (pintype "bidirectional"))
    )
    (net (code "11") (name "/CS_RFM69") (class "Default")
      (node (ref "PCB2") (pin "P$64") (pinfunction "GPIO8_P$64") (pintype "bidirectional"))
      (node (ref "RFM69HCW") (pin "14") (pinfunction "~{SEL}_14") (pintype "input"))
      (node (ref "SJ13") (pin "2") (pinfunction "2_2") (pintype "passive"))
    )
    (net (code "12") (name "/CS_STM32") (class "Default")
      (node (ref "SJ14") (pin "1") (pinfunction "1_1") (pintype "passive"))
      (node (ref "SJ19") (pin "2") (pinfunction "2_2") (pintype "passive"))
      (node (ref "SJ8") (pin "2") (pinfunction "2_2") (pintype "passive"))
    )
    (net (code "13") (name "/CT1") (class "Default")
      (node (ref "CF1") (pin "2") (pinfunction "2_2") (pintype "passive"))
      (node (ref "RF1") (pin "2") (pinfunction "2_2") (pintype "passive"))
      (node (ref "STM32F303VE") (pin "44") (pinfunction "PE13_44") (pintype "bidirectional"))
    )
    (net (code "14") (name "/CT1_EX") (class "Default")
      (node (ref "EXPANSION") (pin "3") (pinfunction "3_3") (pintype "passive"))
      (node (ref "STM32F303VE") (pin "29") (pinfunction "PA4_29") (pintype "bidirectional"))
    )
    (net (code "15") (name "/CT2") (class "Default")
      (node (ref "CF2") (pin "2") (pinfunction "2_2") (pintype "passive"))
      (node (ref "RF2") (pin "2") (pinfunction "2_2") (pintype "passive"))
      (node (ref "STM32F303VE") (pin "43") (pinfunction "PE12_43") (pintype "bidirectional"))
    )
    (net (code "16") (name "/CT2_EX") (class "Default")
      (node (ref "EXPANSION") (pin "6") (pinfunction "6_6") (pintype "passive"))
      (node (ref "STM32F303VE") (pin "30") (pinfunction "PA5_30") (pintype "bidirectional"))
    )
    (net (code "17") (name "/CT3") (class "Default")
      (node (ref "CF3") (pin "2") (pinfunction "2_2") (pintype "passive"))
      (node (ref "RF3") (pin "2") (pinfunction "2_2") (pintype "passive"))
      (node (ref "STM32F303VE") (pin "42") (pinfunction "PE11_42") (pintype "bidirectional"))
    )
    (net (code "18") (name "/CT3_EX") (class "Default")
      (node (ref "EXPANSION") (pin "5") (pinfunction "5_5") (pintype "passive"))
      (node (ref "STM32F303VE") (pin "31") (pinfunction "PA6_31") (pintype "bidirectional"))
    )
    (net (code "19") (name "/CT4") (class "Default")
      (node (ref "CF4") (pin "2") (pinfunction "2_2") (pintype "passive"))
      (node (ref "RF4") (pin "2") (pinfunction "2_2") (pintype "passive"))
      (node (ref "STM32F303VE") (pin "41") (pinfunction "PE10_41") (pintype "bidirectional"))
    )
    (net (code "20") (name "/CT4_EX") (class "Default")
      (node (ref "EXPANSION") (pin "8") (pinfunction "8_8") (pintype "passive"))
      (node (ref "STM32F303VE") (pin "32") (pinfunction "PA7_32") (pintype "bidirectional"))
    )
    (net (code "21") (name "/CT5") (class "Default")
      (node (ref "CF5") (pin "2") (pinfunction "2_2") (pintype "passive"))
      (node (ref "RF5") (pin "2") (pinfunction "2_2") (pintype "passive"))
      (node (ref "STM32F303VE") (pin "40") (pinfunction "PE9_40") (pintype "bidirectional"))
    )
    (net (code "22") (name "/CT5_EX") (class "Default")
      (node (ref "EXPANSION") (pin "7") (pinfunction "7_7") (pintype "passive"))
      (node (ref "STM32F303VE") (pin "33") (pinfunction "PC4_33") (pintype "bidirectional"))
    )
    (net (code "23") (name "/CT6") (class "Default")
      (node (ref "CF6") (pin "2") (pinfunction "2_2") (pintype "passive"))
      (node (ref "RF6") (pin "2") (pinfunction "2_2") (pintype "passive"))
      (node (ref "STM32F303VE") (pin "39") (pinfunction "PE8_39") (pintype "bidirectional"))
    )
    (net (code "24") (name "/CT6_EX") (class "Default")
      (node (ref "EXPANSION") (pin "10") (pinfunction "10_10") (pintype "passive"))
      (node (ref "STM32F303VE") (pin "15") (pinfunction "PC0_15") (pintype "bidirectional"))
    )
    (net (code "25") (name "/CT7") (class "Default")
      (node (ref "CF7") (pin "2") (pinfunction "2_2") (pintype "passive"))
      (node (ref "RF7") (pin "2") (pinfunction "2_2") (pintype "passive"))
      (node (ref "STM32F303VE") (pin "38") (pinfunction "PE7_38") (pintype "bidirectional"))
    )
    (net (code "26") (name "/CT7_EX") (class "Default")
      (node (ref "EXPANSION") (pin "9") (pinfunction "9_9") (pintype "passive"))
      (node (ref "STM32F303VE") (pin "16") (pinfunction "PC1_16") (pintype "bidirectional"))
    )
    (net (code "27") (name "/CT8") (class "Default")
      (node (ref "CF8") (pin "2") (pinfunction "2_2") (pintype "passive"))
      (node (ref "RF8") (pin "2") (pinfunction "2_2") (pintype "passive"))
      (node (ref "STM32F303VE") (pin "36") (pinfunction "PB1_36") (pintype "bidirectional"))
    )
    (net (code "28") (name "/CT9") (class "Default")
      (node (ref "CF9") (pin "2") (pinfunction "2_2") (pintype "passive"))
      (node (ref "RF9") (pin "2") (pinfunction "2_2") (pintype "passive"))
      (node (ref "STM32F303VE") (pin "35") (pinfunction "PB0_35") (pintype "bidirectional"))
    )
    (net (code "29") (name "/D+") (class "Default")
      (node (ref "R6") (pin "2") (pinfunction "2_2") (pintype "passive"))
      (node (ref "STM32F303VE") (pin "71") (pinfunction "PA12_71") (pintype "bidirectional"))
      (node (ref "TP5") (pin "TP") (pinfunction "TP_TP") (pintype "input"))
      (node (ref "USB-C") (pin "A6") (pinfunction "D1+_A6") (pintype "passive"))
    )
    (net (code "30") (name "/D-") (class "Default")
      (node (ref "STM32F303VE") (pin "70") (pinfunction "PA11_70") (pintype "bidirectional"))
      (node (ref "TP6") (pin "TP") (pinfunction "TP_TP") (pintype "input"))
      (node (ref "USB-C") (pin "A7") (pinfunction "D1-_A7") (pintype "passive"))
    )
    (net (code "31") (name "/DIO0") (class "Default")
      (node (ref "PCB2") (pin "P$58") (pinfunction "GPIO24_P$58") (pintype "bidirectional"))
      (node (ref "RFM69HCW") (pin "2") (pinfunction "~{IRQ}_2") (pintype "output"))
      (node (ref "STM32F303VE") (pin "89") (pinfunction "PB3_89") (pintype "bidirectional"))
      (node (ref "U1") (pin "24") (pinfunction "IO2_24") (pintype "bidirectional"))
    )
    (net (code "32") (name "/DS18B20_2_RJ45") (class "Default")
      (node (ref "R7") (pin "1") (pinfunction "1_1") (pintype "passive"))
      (node (ref "RJ45_2") (pin "4") (pinfunction "4_4") (pintype "bidirectional"))
      (node (ref "STM32F303VE") (pin "81") (pinfunction "PD0_81") (pintype "bidirectional"))
    )
    (net (code "33") (name "/DS18B20_RJ45") (class "Default")
      (node (ref "R1") (pin "1") (pinfunction "1_1") (pintype "passive"))
      (node (ref "RJ45_1") (pin "4") (pinfunction "4_4") (pintype "bidirectional"))
      (node (ref "STM32F303VE") (pin "66") (pinfunction "PC9_66") (pintype "bidirectional"))
    )
    (net (code "34") (name "/HSE_IN") (class "Default")
      (node (ref "C30") (pin "1") (pinfunction "1_1") (pintype "passive"))
      (node (ref "HSE") (pin "1") (pinfunction "1_1") (pintype "passive"))
      (node (ref "STM32F303VE") (pin "12") (pinfunction "PF0/OSC_IN_12") (pintype "bidirectional"))
    )
    (net (code "35") (name "/HSE_OUT") (class "Default")
      (node (ref "R21") (pin "1") (pinfunction "1_1") (pintype "passive"))
      (node (ref "STM32F303VE") (pin "13") (pinfunction "PF1/OSC_OUT_13") (pintype "bidirectional"))
    )
    (net (code "36") (name "/HSPICS0") (class "Default")
      (node (ref "SJ13") (pin "1") (pinfunction "1_1") (pintype "passive"))
      (node (ref "U1") (pin "23") (pinfunction "IO15_23") (pintype "bidirectional"))
    )
    (net (code "37") (name "/HSPID") (class "Default")
      (node (ref "SJ9") (pin "1") (pinfunction "1_1") (pintype "passive"))
      (node (ref "U1") (pin "16") (pinfunction "IO13_16") (pintype "bidirectional"))
    )
    (net (code "38") (name "/HSPIQ") (class "Default")
      (node (ref "SJ4") (pin "1") (pinfunction "1_1") (pintype "passive"))
      (node (ref "U1") (pin "14") (pinfunction "IO12_14") (pintype "bidirectional"))
    )
    (net (code "39") (name "/HSPI_CLK") (class "Default")
      (node (ref "SJ10") (pin "1") (pinfunction "1_1") (pintype "passive"))
      (node (ref "U1") (pin "13") (pinfunction "IO14_13") (pintype "bidirectional"))
    )
    (net (code "40") (name "/IO1_EX") (class "Default")
      (node (ref "EXPANSION") (pin "15") (pinfunction "15_15") (pintype "passive"))
      (node (ref "STM32F303VE") (pin "97") (pinfunction "PE0_97") (pintype "bidirectional"))
    )
    (net (code "41") (name "/IO2_EX") (class "Default")
      (node (ref "EXPANSION") (pin "16") (pinfunction "16_16") (pintype "passive"))
      (node (ref "STM32F303VE") (pin "98") (pinfunction "PE1_98") (pintype "bidirectional"))
    )
    (net (code "42") (name "/IO3_EX") (class "Default")
      (node (ref "EXPANSION") (pin "17") (pinfunction "17_17") (pintype "passive"))
      (node (ref "STM32F303VE") (pin "1") (pinfunction "PE2_1") (pintype "bidirectional"))
    )
    (net (code "43") (name "/IO4_EX") (class "Default")
      (node (ref "EXPANSION") (pin "18") (pinfunction "18_18") (pintype "passive"))
      (node (ref "STM32F303VE") (pin "2") (pinfunction "PE3_2") (pintype "bidirectional"))
    )
    (net (code "44") (name "/IO5_EX") (class "Default")
      (node (ref "EXPANSION") (pin "19") (pinfunction "19_19") (pintype "passive"))
      (node (ref "STM32F303VE") (pin "3") (pinfunction "PE4_3") (pintype "bidirectional"))
    )
    (net (code "45") (name "/IO6_EX") (class "Default")
      (node (ref "EXPANSION") (pin "21") (pinfunction "21_21") (pintype "passive"))
      (node (ref "STM32F303VE") (pin "4") (pinfunction "PE5_4") (pintype "bidirectional"))
    )
    (net (code "46") (name "/IO7_EX") (class "Default")
      (node (ref "EXPANSION") (pin "23") (pinfunction "23_23") (pintype "passive"))
      (node (ref "STM32F303VE") (pin "5") (pinfunction "PE6_5") (pintype "bidirectional"))
    )
    (net (code "47") (name "/IO8_EX") (class "Default")
      (node (ref "STM32F303VE") (pin "91") (pinfunction "PB5_91") (pintype "bidirectional"))
    )
    (net (code "48") (name "/IO11_EX") (class "Default")
      (node (ref "STM32F303VE") (pin "95") (pinfunction "PB8_95") (pintype "bidirectional"))
    )
    (net (code "49") (name "/LED1_GREEN") (class "Default")
      (node (ref "R3") (pin "2") (pinfunction "2_2") (pintype "passive"))
      (node (ref "STM32F303VE") (pin "55") (pinfunction "PD8_55") (pintype "bidirectional"))
    )
    (net (code "50") (name "/LED2_YELLOW") (class "Default")
      (node (ref "R4") (pin "2") (pinfunction "2_2") (pintype "passive"))
      (node (ref "STM32F303VE") (pin "56") (pinfunction "PD9_56") (pintype "bidirectional"))
    )
    (net (code "51") (name "/LED3_RED") (class "Default")
      (node (ref "R5") (pin "2") (pinfunction "2_2") (pintype "passive"))
      (node (ref "STM32F303VE") (pin "57") (pinfunction "PD10_57") (pintype "bidirectional"))
    )
    (net (code "52") (name "/MBUS_I{slash}O") (class "Default")
      (node (ref "Q1") (pin "2") (pinfunction "E_2") (pintype "passive"))
      (node (ref "R17") (pin "1") (pinfunction "1_1") (pintype "passive"))
      (node (ref "U$6") (pin "P$2") (pinfunction "P$2_P$2") (pintype "bidirectional"))
    )
    (net (code "53") (name "/MBUS_RX") (class "Default")
      (node (ref "R18") (pin "2") (pinfunction "2_2") (pintype "passive"))
      (node (ref "SJ11") (pin "2") (pinfunction "2_2") (pintype "passive"))
      (node (ref "SJ33") (pin "2") (pinfunction "2_2") (pintype "passive"))
    )
    (net (code "54") (name "/MBUS_TX") (class "Default")
      (node (ref "R19") (pin "2") (pinfunction "2_2") (pintype "passive"))
      (node (ref "SJ12") (pin "2") (pinfunction "2_2") (pintype "passive"))
      (node (ref "SJ31") (pin "2") (pinfunction "2_2") (pintype "passive"))
    )
    (net (code "55") (name "/MISO") (class "Default")
      (node (ref "RFM69HCW") (pin "1") (pinfunction "SDO_1") (pintype "output"))
      (node (ref "SJ16") (pin "2") (pinfunction "2_2") (pintype "passive"))
      (node (ref "SJ4") (pin "2") (pinfunction "2_2") (pintype "passive"))
      (node (ref "SJ6") (pin "1") (pinfunction "1_1") (pintype "passive"))
    )
    (net (code "56") (name "/MOSI") (class "Default")
      (node (ref "RFM69HCW") (pin "12") (pinfunction "SDI_12") (pintype "input"))
      (node (ref "SJ17") (pin "2") (pinfunction "2_2") (pintype "passive"))
      (node (ref "SJ5") (pin "1") (pinfunction "1_1") (pintype "passive"))
      (node (ref "SJ9") (pin "2") (pinfunction "2_2") (pintype "passive"))
    )
    (net (code "57") (name "/NRST_STM") (class "Default")
      (node (ref "S2") (pin "2") (pinfunction "2_2") (pintype "bidirectional"))
      (node (ref "SJ25") (pin "2") (pinfunction "2_2") (pintype "passive"))
      (node (ref "SJ32") (pin "1") (pinfunction "1_1") (pintype "passive"))
      (node (ref "STM32F303VE") (pin "14") (pinfunction "NRST_14") (pintype "bidirectional"))
      (node (ref "SV1") (pin "6") (pinfunction "6_6") (pintype "passive"))
    )
    (net (code "58") (name "/PC14") (class "Default")
      (node (ref "C31") (pin "1") (pinfunction "1_1") (pintype "passive"))
      (node (ref "LSE") (pin "P$1") (pinfunction "1_P$1") (pintype "passive"))
      (node (ref "STM32F303VE") (pin "8") (pinfunction "PC14/OSC32_IN_8") (pintype "bidirectional"))
    )
    (net (code "59") (name "/PC15") (class "Default")
      (node (ref "C32") (pin "1") (pinfunction "1_1") (pintype "passive"))
      (node (ref "LSE") (pin "P$4") (pinfunction "2_P$4") (pintype "passive"))
      (node (ref "STM32F303VE") (pin "9") (pinfunction "PC15/OSC32_OUT_9") (pintype "bidirectional"))
    )
    (net (code "60") (name "/PULSE1_RJ45") (class "Default")
      (node (ref "C41") (pin "1") (pinfunction "1_1") (pintype "passive"))
      (node (ref "RJ45_1") (pin "6") (pinfunction "6_6") (pintype "bidirectional"))
      (node (ref "STM32F303VE") (pin "67") (pinfunction "PA8_67") (pintype "bidirectional"))
    )
    (net (code "61") (name "/PULSE_2_RJ45") (class "Default")
      (node (ref "C46") (pin "1") (pinfunction "1_1") (pintype "passive"))
      (node (ref "RJ45_2") (pin "6") (pinfunction "6_6") (pintype "bidirectional"))
    )
    (net (code "62") (name "/PUSHIN_1") (class "Default")
      (node (ref "C1") (pin "1") (pinfunction "1_1") (pintype "passive"))
      (node (ref "D17") (pin "K") (pinfunction "C_K") (pintype "passive"))
      (node (ref "STM32F303VE") (pin "63") (pinfunction "PC6_63") (pintype "bidirectional"))
      (node (ref "U$1") (pin "P$2") (pinfunction "P$2_P$2") (pintype "bidirectional"))
    )
    (net (code "63") (name "/PUSHIN_2") (class "Default")
      (node (ref "C19") (pin "1") (pinfunction "1_1") (pintype "passive"))
      (node (ref "D18") (pin "K") (pinfunction "C_K") (pintype "passive"))
      (node (ref "STM32F303VE") (pin "64") (pinfunction "PC7_64") (pintype "bidirectional"))
      (node (ref "U$3") (pin "P$2") (pinfunction "P$2_P$2") (pintype "bidirectional"))
    )
    (net (code "64") (name "/PUSHIN_3") (class "Default")
      (node (ref "C20") (pin "1") (pinfunction "1_1") (pintype "passive"))
      (node (ref "D21") (pin "K") (pinfunction "C_K") (pintype "passive"))
      (node (ref "STM32F303VE") (pin "65") (pinfunction "PC8_65") (pintype "bidirectional"))
      (node (ref "U$4") (pin "P$2") (pinfunction "P$2_P$2") (pintype "bidirectional"))
    )
    (net (code "65") (name "/PUSHIN_BYANT") (class "Default")
      (node (ref "C22") (pin "1") (pinfunction "1_1") (pintype "passive"))
      (node (ref "D26") (pin "K") (pinfunction "C_K") (pintype "passive"))
      (node (ref "STM32F303VE") (pin "96") (pinfunction "PB9_96") (pintype "bidirectional"))
      (node (ref "U$5") (pin "P$2") (pinfunction "P$2_P$2") (pintype "bidirectional"))
    )
    (net (code "66") (name "/RPI_GPIO16") (class "Default")
      (node (ref "SJ29") (pin "2") (pinfunction "2_2") (pintype "passive"))
      (node (ref "STM32F303VE") (pin "59") (pinfunction "PD12_59") (pintype "bidirectional"))
    )
    (net (code "67") (name "/RPI_GPIO20") (class "Default")
      (node (ref "SJ30") (pin "2") (pinfunction "2_2") (pintype "passive"))
      (node (ref "STM32F303VE") (pin "60") (pinfunction "PD13_60") (pintype "bidirectional"))
    )
    (net (code "68") (name "/RPI_MISO") (class "Default")
      (node (ref "PCB2") (pin "P$61") (pinfunction "GPIO9_P$61") (pintype "bidirectional"))
      (node (ref "SJ6") (pin "2") (pinfunction "2_2") (pintype "passive"))
    )
    (net (code "69") (name "/RPI_MOSI") (class "Default")
      (node (ref "PCB2") (pin "P$59") (pinfunction "GPIO10_P$59") (pintype "bidirectional"))
      (node (ref "SJ5") (pin "2") (pinfunction "2_2") (pintype "passive"))
    )
    (net (code "70") (name "/RPI_SPI_CLK") (class "Default")
      (node (ref "PCB2") (pin "P$63") (pinfunction "GPIO11_P$63") (pintype "bidirectional"))
      (node (ref "SJ7") (pin "2") (pinfunction "2_2") (pintype "passive"))
    )
    (net (code "71") (name "/RST_RFM") (class "Default")
      (node (ref "RFM69HCW") (pin "6") (pinfunction "~{RES}_6") (pintype "bidirectional"))
      (node (ref "SJ24") (pin "2") (pinfunction "2_2") (pintype "passive"))
      (node (ref "SJ28") (pin "1") (pinfunction "1_1") (pintype "passive"))
    )
    (net (code "72") (name "/RXD0_ESP") (class "Default")
      (node (ref "SJ18") (pin "1") (pinfunction "1_1") (pintype "passive"))
      (node (ref "SJ21") (pin "2") (pinfunction "2_2") (pintype "passive"))
      (node (ref "SV2") (pin "4") (pinfunction "4_4") (pintype "passive"))
      (node (ref "U1") (pin "34") (pinfunction "RXD0_34") (pintype "bidirectional"))
    )
    (net (code "73") (name "/SCL") (class "Default")
      (node (ref "EXPANSION") (pin "22") (pinfunction "22_22") (pintype "passive"))
      (node (ref "OLED") (pin "2") (pinfunction "2_2") (pintype "passive"))
      (node (ref "R13") (pin "2") (pinfunction "2_2") (pintype "passive"))
      (node (ref "SJ27") (pin "2") (pinfunction "2_2") (pintype "passive"))
      (node (ref "STM32F303VE") (pin "92") (pinfunction "PB6_92") (pintype "bidirectional"))
      (node (ref "U1") (pin "36") (pinfunction "IO22_36") (pintype "bidirectional"))
    )
    (net (code "74") (name "/SDA") (class "Default")
      (node (ref "EXPANSION") (pin "20") (pinfunction "20_20") (pintype "passive"))
      (node (ref "OLED") (pin "1") (pinfunction "1_1") (pintype "passive"))
      (node (ref "R20") (pin "2") (pinfunction "2_2") (pintype "passive"))
      (node (ref "SJ26") (pin "1") (pinfunction "1_1") (pintype "passive"))
      (node (ref "STM32F303VE") (pin "93") (pinfunction "PB7_93") (pintype "bidirectional"))
      (node (ref "U1") (pin "33") (pinfunction "IO21_33") (pintype "bidirectional"))
    )
    (net (code "75") (name "/SPI3_CLK") (class "Default")
      (node (ref "SJ15") (pin "1") (pinfunction "1_1") (pintype "passive"))
      (node (ref "STM32F303VE") (pin "78") (pinfunction "PC10_78") (pintype "bidirectional"))
    )
    (net (code "76") (name "/SPI3_CS") (class "Default")
      (node (ref "SJ14") (pin "2") (pinfunction "2_2") (pintype "passive"))
      (node (ref "STM32F303VE") (pin "77") (pinfunction "PA15_77") (pintype "bidirectional"))
    )
    (net (code "77") (name "/SPI3_CS_ESP") (class "Default")
      (node (ref "STM32F303VE") (pin "84") (pinfunction "PD3_84") (pintype "bidirectional"))
    )
    (net (code "78") (name "/SPI3_MISO") (class "Default")
      (node (ref "SJ16") (pin "1") (pinfunction "1_1") (pintype "passive"))
      (node (ref "STM32F303VE") (pin "79") (pinfunction "PC11_79") (pintype "bidirectional"))
    )
    (net (code "79") (name "/SPI3_MOSI") (class "Default")
      (node (ref "SJ17") (pin "1") (pinfunction "1_1") (pintype "passive"))
      (node (ref "STM32F303VE") (pin "80") (pinfunction "PC12_80") (pintype "bidirectional"))
    )
    (net (code "80") (name "/SPI_CLK") (class "Default")
      (node (ref "RFM69HCW") (pin "13") (pinfunction "SCK_13") (pintype "input"))
      (node (ref "SJ10") (pin "2") (pinfunction "2_2") (pintype "passive"))
      (node (ref "SJ15") (pin "2") (pinfunction "2_2") (pintype "passive"))
      (node (ref "SJ7") (pin "1") (pinfunction "1_1") (pintype "passive"))
    )
    (net (code "81") (name "/SWCLK") (class "Default")
      (node (ref "STM32F303VE") (pin "76") (pinfunction "PA14_76") (pintype "bidirectional"))
      (node (ref "ST_LINK") (pin "1") (pinfunction "1_1") (pintype "passive"))
    )
    (net (code "82") (name "/SWDIO") (class "Default")
      (node (ref "STM32F303VE") (pin "72") (pinfunction "PA13_72") (pintype "bidirectional"))
      (node (ref "ST_LINK") (pin "2") (pinfunction "2_2") (pintype "passive"))
    )
    (net (code "83") (name "/TXD0_ESP") (class "Default")
      (node (ref "SJ20") (pin "2") (pinfunction "2_2") (pintype "passive"))
      (node (ref "SJ3") (pin "1") (pinfunction "1_1") (pintype "passive"))
      (node (ref "SV2") (pin "5") (pinfunction "5_5") (pintype "passive"))
      (node (ref "U1") (pin "35") (pinfunction "TXD0_35") (pintype "bidirectional"))
    )
    (net (code "84") (name "/UART1_RX") (class "Default")
      (node (ref "PCB2") (pin "P$48") (pinfunction "GPIO14_P$48") (pintype "bidirectional"))
      (node (ref "SJ11") (pin "1") (pinfunction "1_1") (pintype "passive"))
      (node (ref "SJ20") (pin "1") (pinfunction "1_1") (pintype "passive"))
      (node (ref "STM32F303VE") (pin "69") (pinfunction "PA10_69") (pintype "bidirectional"))
      (node (ref "UART1") (pin "1") (pinfunction "1_1") (pintype "passive"))
    )
    (net (code "85") (name "/UART1_TX") (class "Default")
      (node (ref "PCB2") (pin "P$50") (pinfunction "GPIO15_P$50") (pintype "bidirectional"))
      (node (ref "SJ12") (pin "1") (pinfunction "1_1") (pintype "passive"))
      (node (ref "SJ21") (pin "1") (pinfunction "1_1") (pintype "passive"))
      (node (ref "STM32F303VE") (pin "68") (pinfunction "PA9_68") (pintype "bidirectional"))
      (node (ref "UART1") (pin "2") (pinfunction "2_2") (pintype "passive"))
    )
    (net (code "86") (name "/UART2_RX") (class "Default")
      (node (ref "STM32F303VE") (pin "26") (pinfunction "PA3_26") (pintype "bidirectional"))
      (node (ref "SV1") (pin "4") (pinfunction "4_4") (pintype "passive"))
    )
    (net (code "87") (name "/UART2_TX") (class "Default")
      (node (ref "STM32F303VE") (pin "25") (pinfunction "PA2_25") (pintype "bidirectional"))
      (node (ref "STM32F303VE") (pin "86") (pinfunction "PD5_86") (pintype "bidirectional"))
      (node (ref "SV1") (pin "5") (pinfunction "5_5") (pintype "passive"))
    )
    (net (code "88") (name "/USART3_RX") (class "Default")
      (node (ref "SJ3") (pin "2") (pinfunction "2_2") (pintype "passive"))
      (node (ref "STM32F303VE") (pin "48") (pinfunction "PB11_48") (pintype "bidirectional"))
    )
    (net (code "89") (name "/USART3_TX") (class "Default")
      (node (ref "SJ18") (pin "2") (pinfunction "2_2") (pintype "passive"))
      (node (ref "STM32F303VE") (pin "47") (pinfunction "PB10_47") (pintype "bidirectional"))
    )
    (net (code "90") (name "/VBAT") (class "Default")
      (node (ref "G1") (pin "+") (pinfunction "+_+") (pintype "passive"))
      (node (ref "R8") (pin "2") (pinfunction "2_2") (pintype "passive"))
      (node (ref "STM32F303VE") (pin "6") (pinfunction "VBAT_6") (pintype "bidirectional"))
    )
    (net (code "91") (name "/VREF+") (class "Default")
      (node (ref "C23") (pin "1") (pinfunction "1_1") (pintype "passive"))
      (node (ref "JP1") (pin "3") (pinfunction "3_3") (pintype "passive"))
      (node (ref "SJ2") (pin "2") (pinfunction "2_2") (pintype "passive"))
      (node (ref "STM32F303VE") (pin "21") (pinfunction "VREF+_21") (pintype "bidirectional"))
      (node (ref "VREF_3V3") (pin "1") (pinfunction "OUT_1") (pintype "bidirectional"))
    )
    (net (code "92") (name "/VSIG1") (class "Default")
      (node (ref "CV1") (pin "1") (pinfunction "1_1") (pintype "passive"))
      (node (ref "D2") (pin "K") (pinfunction "C_K") (pintype "passive"))
      (node (ref "RV1") (pin "2") (pinfunction "2_2") (pintype "passive"))
      (node (ref "STM32F303VE") (pin "23") (pinfunction "PA0_23") (pintype "bidirectional"))
    )
    (net (code "93") (name "/VSIG2") (class "Default")
      (node (ref "CV2") (pin "1") (pinfunction "1_1") (pintype "passive"))
      (node (ref "D3") (pin "K") (pinfunction "C_K") (pintype "passive"))
      (node (ref "RV2") (pin "2") (pinfunction "2_2") (pintype "passive"))
      (node (ref "STM32F303VE") (pin "24") (pinfunction "PA1_24") (pintype "bidirectional"))
    )
    (net (code "94") (name "/VSIG3") (class "Default")
      (node (ref "CV3") (pin "1") (pinfunction "1_1") (pintype "passive"))
      (node (ref "D4") (pin "K") (pinfunction "C_K") (pintype "passive"))
      (node (ref "RV3") (pin "2") (pinfunction "2_2") (pintype "passive"))
      (node (ref "STM32F303VE") (pin "27") (pinfunction "PF4_27") (pintype "bidirectional"))
    )
    (net (code "95") (name "/VSIG4") (class "Default")
      (node (ref "EXPANSION") (pin "11") (pinfunction "11_11") (pintype "passive"))
      (node (ref "STM32F303VE") (pin "17") (pinfunction "PC2_17") (pintype "bidirectional"))
    )
    (net (code "96") (name "/VSIG5") (class "Default")
      (node (ref "EXPANSION") (pin "12") (pinfunction "12_12") (pintype "passive"))
      (node (ref "STM32F303VE") (pin "18") (pinfunction "PC3_18") (pintype "bidirectional"))
    )
    (net (code "97") (name "/VSIG6") (class "Default")
      (node (ref "EXPANSION") (pin "13") (pinfunction "13_13") (pintype "passive"))
      (node (ref "STM32F303VE") (pin "19") (pinfunction "PF2_19") (pintype "bidirectional"))
    )
    (net (code "98") (name "GND") (class "Default")
      (node (ref "BOOT_ESP") (pin "1") (pinfunction "1_1") (pintype "passive"))
      (node (ref "C1") (pin "2") (pinfunction "2_2") (pintype "passive"))
      (node (ref "C10") (pin "2") (pinfunction "2_2") (pintype "passive"))
      (node (ref "C11") (pin "2") (pinfunction "2_2") (pintype "passive"))
      (node (ref "C12") (pin "1") (pinfunction "1_1") (pintype "passive"))
      (node (ref "C13") (pin "2") (pinfunction "2_2") (pintype "passive"))
      (node (ref "C14") (pin "2") (pinfunction "2_2") (pintype "passive"))
      (node (ref "C15") (pin "1") (pinfunction "1_1") (pintype "passive"))
      (node (ref "C17") (pin "2") (pinfunction "2_2") (pintype "passive"))
      (node (ref "C18") (pin "2") (pinfunction "2_2") (pintype "passive"))
      (node (ref "C19") (pin "2") (pinfunction "2_2") (pintype "passive"))
      (node (ref "C2") (pin "2") (pinfunction "2_2") (pintype "passive"))
      (node (ref "C20") (pin "2") (pinfunction "2_2") (pintype "passive"))
      (node (ref "C21") (pin "2") (pinfunction "2_2") (pintype "passive"))
      (node (ref "C22") (pin "2") (pinfunction "2_2") (pintype "passive"))
      (node (ref "C23") (pin "2") (pinfunction "2_2") (pintype "passive"))
      (node (ref "C24") (pin "2") (pinfunction "2_2") (pintype "passive"))
      (node (ref "C25") (pin "2") (pinfunction "2_2") (pintype "passive"))
      (node (ref "C26") (pin "2") (pinfunction "2_2") (pintype "passive"))
      (node (ref "C27") (pin "2") (pinfunction "2_2") (pintype "passive"))
      (node (ref "C28") (pin "2") (pinfunction "2_2") (pintype "passive"))
      (node (ref "C29") (pin "2") (pinfunction "2_2") (pintype "passive"))
      (node (ref "C3") (pin "2") (pinfunction "2_2") (pintype "passive"))
      (node (ref "C30") (pin "2") (pinfunction "2_2") (pintype "passive"))
      (node (ref "C31") (pin "2") (pinfunction "2_2") (pintype "passive"))
      (node (ref "C32") (pin "2") (pinfunction "2_2") (pintype "passive"))
      (node (ref "C4") (pin "1") (pinfunction "1_1") (pintype "passive"))
      (node (ref "C40") (pin "2") (pinfunction "2_2") (pintype "passive"))
      (node (ref "C41") (pin "2") (pinfunction "2_2") (pintype "passive"))
      (node (ref "C42") (pin "2") (pinfunction "2_2") (pintype "passive"))
      (node (ref "C45") (pin "2") (pinfunction "2_2") (pintype "passive"))
      (node (ref "C46") (pin "2") (pinfunction "2_2") (pintype "passive"))
      (node (ref "C47") (pin "2") (pinfunction "2_2") (pintype "passive"))
      (node (ref "C5") (pin "1") (pinfunction "1_1") (pintype "passive"))
      (node (ref "C50*") (pin "1") (pinfunction "1_1") (pintype "passive"))
      (node (ref "C6") (pin "1") (pinfunction "1_1") (pintype "passive"))
      (node (ref "C7") (pin "2") (pinfunction "2_2") (pintype "passive"))
      (node (ref "C8") (pin "1") (pinfunction "1_1") (pintype "passive"))
      (node (ref "C9") (pin "1") (pinfunction "1_1") (pintype "passive"))
      (node (ref "CF1") (pin "1") (pinfunction "1_1") (pintype "passive"))
      (node (ref "CF2") (pin "1") (pinfunction "1_1") (pintype "passive"))
      (node (ref "CF3") (pin "1") (pinfunction "1_1") (pintype "passive"))
      (node (ref "CF4") (pin "1") (pinfunction "1_1") (pintype "passive"))
      (node (ref "CF5") (pin "1") (pinfunction "1_1") (pintype "passive"))
      (node (ref "CF6") (pin "1") (pinfunction "1_1") (pintype "passive"))
      (node (ref "CF7") (pin "1") (pinfunction "1_1") (pintype "passive"))
      (node (ref "CF8") (pin "1") (pinfunction "1_1") (pintype "passive"))
      (node (ref "CF9") (pin "1") (pinfunction "1_1") (pintype "passive"))
      (node (ref "CV1") (pin "2") (pinfunction "2_2") (pintype "passive"))
      (node (ref "CV2") (pin "2") (pinfunction "2_2") (pintype "passive"))
      (node (ref "CV3") (pin "2") (pinfunction "2_2") (pintype "passive"))
      (node (ref "D1") (pin "A") (pinfunction "A_A") (pintype "passive"))
      (node (ref "D10") (pin "A") (pinfunction "A_A") (pintype "passive"))
      (node (ref "D11") (pin "A") (pinfunction "A_A") (pintype "passive"))
      (node (ref "D12") (pin "A") (pinfunction "A_A") (pintype "passive"))
      (node (ref "D13") (pin "A") (pinfunction "A_A") (pintype "passive"))
      (node (ref "D17") (pin "A") (pinfunction "A_A") (pintype "passive"))
      (node (ref "D18") (pin "A") (pinfunction "A_A") (pintype "passive"))
      (node (ref "D2") (pin "A") (pinfunction "A_A") (pintype "passive"))
      (node (ref "D21") (pin "A") (pinfunction "A_A") (pintype "passive"))
      (node (ref "D22") (pin "A") (pinfunction "A_A") (pintype "passive"))
      (node (ref "D23") (pin "A") (pinfunction "A_A") (pintype "passive"))
      (node (ref "D26") (pin "A") (pinfunction "A_A") (pintype "passive"))
      (node (ref "D3") (pin "A") (pinfunction "A_A") (pintype "passive"))
      (node (ref "D4") (pin "A") (pinfunction "A_A") (pintype "passive"))
      (node (ref "D40*1") (pin "A") (pinfunction "A_A") (pintype "passive"))
      (node (ref "D5") (pin "A") (pinfunction "A_A") (pintype "passive"))
      (node (ref "D6") (pin "A") (pinfunction "A_A") (pintype "passive"))
      (node (ref "D7") (pin "A") (pinfunction "A_A") (pintype "passive"))
      (node (ref "D8") (pin "A") (pinfunction "A_A") (pintype "passive"))
      (node (ref "D9") (pin "A") (pinfunction "A_A") (pintype "passive"))
      (node (ref "EXPANSION") (pin "1") (pinfunction "1_1") (pintype "passive"))
      (node (ref "EXPANSION") (pin "14") (pinfunction "14_14") (pintype "passive"))
      (node (ref "EXPANSION") (pin "2") (pinfunction "2_2") (pintype "passive"))
      (node (ref "EXPANSION") (pin "25") (pinfunction "25_25") (pintype "passive"))
      (node (ref "G1") (pin "-") (pinfunction "-_-") (pintype "passive"))
      (node (ref "J$1") (pin "GND@0") (pinfunction "GND_GND@0") (pintype "bidirectional"))
      (node (ref "J$1") (pin "GND@1") (pinfunction "GND_GND@1") (pintype "bidirectional"))
      (node (ref "J$1") (pin "GND@2") (pinfunction "GND_GND@2") (pintype "bidirectional"))
      (node (ref "J$1") (pin "GND@3") (pinfunction "GND_GND@3") (pintype "bidirectional"))
      (node (ref "LED1") (pin "C") (pinfunction "C_C") (pintype "passive"))
      (node (ref "LED2") (pin "C") (pinfunction "C_C") (pintype "passive"))
      (node (ref "LED3") (pin "C") (pinfunction "C_C") (pintype "passive"))
      (node (ref "LED4") (pin "C") (pinfunction "C_C") (pintype "passive"))
      (node (ref "MCP1825") (pin "2") (pinfunction "GND_2") (pintype "power_in"))
      (node (ref "MCP1825") (pin "4") (pinfunction "GND_4") (pintype "power_in"))
      (node (ref "OLED") (pin "4") (pinfunction "4_4") (pintype "passive"))
      (node (ref "PCB2") (pin "P$46") (pinfunction "GND_P$46") (pintype "bidirectional"))
      (node (ref "PCB2") (pin "P$49") (pinfunction "GND_P$49") (pintype "bidirectional"))
      (node (ref "PCB2") (pin "P$54") (pinfunction "GND_P$54") (pintype "bidirectional"))
      (node (ref "PCB2") (pin "P$60") (pinfunction "GND_P$60") (pintype "bidirectional"))
      (node (ref "PCB2") (pin "P$65") (pinfunction "GND_P$65") (pintype "bidirectional"))
      (node (ref "PCB2") (pin "P$70") (pinfunction "GND_P$70") (pintype "bidirectional"))
      (node (ref "PCB2") (pin "P$74") (pinfunction "GND_P$74") (pintype "bidirectional"))
      (node (ref "PCB2") (pin "P$79") (pinfunction "GND_P$79") (pintype "bidirectional"))
      (node (ref "Q2") (pin "2") (pinfunction "E_2") (pintype "passive"))
      (node (ref "Q3") (pin "2") (pinfunction "E_2") (pintype "passive"))
      (node (ref "Q4") (pin "1") (pinfunction "G_1") (pintype "passive"))
      (node (ref "R14") (pin "1") (pinfunction "1_1") (pintype "passive"))
      (node (ref "R15") (pin "1") (pinfunction "1_1") (pintype "passive"))
      (node (ref "R16") (pin "1") (pinfunction "1_1") (pintype "passive"))
      (node (ref "R2") (pin "2") (pinfunction "2_2") (pintype "passive"))
      (node (ref "R23") (pin "1") (pinfunction "1_1") (pintype "passive"))
      (node (ref "RFM69HCW") (pin "10") (pinfunction "GND_10") (pintype "passive"))
      (node (ref "RFM69HCW") (pin "7") (pinfunction "GND_7") (pintype "passive"))
      (node (ref "RJ45_1") (pin "1") (pinfunction "1_1") (pintype "bidirectional"))
      (node (ref "RJ45_1") (pin "3") (pinfunction "3_3") (pintype "bidirectional"))
      (node (ref "RJ45_1") (pin "5") (pinfunction "5_5") (pintype "bidirectional"))
      (node (ref "RJ45_2") (pin "1") (pinfunction "1_1") (pintype "bidirectional"))
      (node (ref "RJ45_2") (pin "3") (pinfunction "3_3") (pintype "bidirectional"))
      (node (ref "RJ45_2") (pin "5") (pinfunction "5_5") (pintype "bidirectional"))
      (node (ref "S1") (pin "1") (pinfunction "1_1") (pintype "bidirectional"))
      (node (ref "S2") (pin "1") (pinfunction "1_1") (pintype "bidirectional"))
      (node (ref "STM32F303VE") (pin "20") (pinfunction "VSSA/VREF-_20") (pintype "bidirectional"))
      (node (ref "STM32F303VE") (pin "49") (pinfunction "VSS_49") (pintype "bidirectional"))
      (node (ref "STM32F303VE") (pin "74") (pinfunction "VSS_74") (pintype "bidirectional"))
      (node (ref "STM32F303VE") (pin "99") (pinfunction "VSS_99") (pintype "bidirectional"))
      (node (ref "SV1") (pin "1") (pinfunction "1_1") (pintype "passive"))
      (node (ref "SV2") (pin "1") (pinfunction "1_1") (pintype "passive"))
      (node (ref "U$1") (pin "P$3") (pinfunction "P$1_P$3") (pintype "bidirectional"))
      (node (ref "U$2") (pin "P$1") (pinfunction "GND_P$1") (pintype "bidirectional"))
      (node (ref "U$2") (pin "P$2") (pinfunction "GND._P$2") (pintype "bidirectional"))
      (node (ref "U$3") (pin "P$3") (pinfunction "P$1_P$3") (pintype "bidirectional"))
      (node (ref "U$4") (pin "P$3") (pinfunction "P$1_P$3") (pintype "bidirectional"))
      (node (ref "U$5") (pin "P$3") (pinfunction "P$1_P$3") (pintype "bidirectional"))
      (node (ref "U$6") (pin "P$3") (pinfunction "P$1_P$3") (pintype "bidirectional"))
      (node (ref "U1") (pin "1") (pinfunction "GND_1") (pintype "power_in"))
      (node (ref "U1") (pin "15") (pinfunction "GND_15") (pintype "power_in"))
      (node (ref "U1") (pin "31") (pinfunction "IO19_31") (pintype "bidirectional"))
      (node (ref "U1") (pin "38") (pinfunction "GND_38") (pintype "power_in"))
      (node (ref "U1") (pin "39") (pinfunction "GND_39") (pintype "power_in"))
      (node (ref "USB-C") (pin "A1/B12") (pinfunction "GND1_A1/B12") (pintype "passive"))
      (node (ref "USB-C") (pin "B1/A12") (pinfunction "GND2_B1/A12") (pintype "passive"))
      (node (ref "USB-C") (pin "GND1") (pinfunction "SHIELD_GND1") (pintype "bidirectional"))
      (node (ref "USB-C") (pin "GND2") (pinfunction "SHIELD_GND2") (pintype "bidirectional"))
      (node (ref "USB-C") (pin "GND3") (pinfunction "SHIELD_GND3") (pintype "bidirectional"))
      (node (ref "USB-C") (pin "GND4") (pinfunction "SHIELD_GND4") (pintype "bidirectional"))
      (node (ref "VREF_3V3") (pin "2") (pinfunction "GND_2") (pintype "bidirectional"))
      (node (ref "VREF_3V3") (pin "3") (pinfunction "GND_3") (pintype "bidirectional"))
      (node (ref "VREF_3V3") (pin "5") (pinfunction "GND_5") (pintype "bidirectional"))
    )
    (net (code "99") (name "Net-(C16-Pad1)") (class "Default")
      (node (ref "C16") (pin "1") (pinfunction "1_1") (pintype "passive"))
      (node (ref "SV2") (pin "6") (pinfunction "6_6") (pintype "passive"))
    )
    (net (code "100") (name "Net-(CT1-2)") (class "Default")
      (node (ref "CT1") (pin "P$2") (pinfunction "2_P$2") (pintype "bidirectional"))
      (node (ref "D13") (pin "K") (pinfunction "C_K") (pintype "passive"))
      (node (ref "RB18") (pin "1") (pinfunction "1_1") (pintype "passive"))
      (node (ref "RB9") (pin "1") (pinfunction "1_1") (pintype "passive"))
      (node (ref "RF9") (pin "1") (pinfunction "1_1") (pintype "passive"))
    )
    (net (code "101") (name "Net-(CT2-2)") (class "Default")
      (node (ref "CT2") (pin "P$2") (pinfunction "2_P$2") (pintype "bidirectional"))
      (node (ref "D12") (pin "K") (pinfunction "C_K") (pintype "passive"))
      (node (ref "RB17") (pin "1") (pinfunction "1_1") (pintype "passive"))
      (node (ref "RB8") (pin "1") (pinfunction "1_1") (pintype "passive"))
      (node (ref "RF8") (pin "1") (pinfunction "1_1") (pintype "passive"))
    )
    (net (code "102") (name "Net-(CT3-2)") (class "Default")
      (node (ref "CT3") (pin "P$2") (pinfunction "2_P$2") (pintype "bidirectional"))
      (node (ref "D11") (pin "K") (pinfunction "C_K") (pintype "passive"))
      (node (ref "RB16") (pin "1") (pinfunction "1_1") (pintype "passive"))
      (node (ref "RB7") (pin "1") (pinfunction "1_1") (pintype "passive"))
      (node (ref "RF7") (pin "1") (pinfunction "1_1") (pintype "passive"))
    )
    (net (code "103") (name "Net-(CT4-2)") (class "Default")
      (node (ref "CT4") (pin "P$2") (pinfunction "2_P$2") (pintype "bidirectional"))
      (node (ref "D10") (pin "K") (pinfunction "C_K") (pintype "passive"))
      (node (ref "RB13") (pin "1") (pinfunction "1_1") (pintype "passive"))
      (node (ref "RB6") (pin "1") (pinfunction "1_1") (pintype "passive"))
      (node (ref "RF6") (pin "1") (pinfunction "1_1") (pintype "passive"))
    )
    (net (code "104") (name "Net-(CT5-2)") (class "Default")
      (node (ref "CT5") (pin "P$2") (pinfunction "2_P$2") (pintype "bidirectional"))
      (node (ref "D9") (pin "K") (pinfunction "C_K") (pintype "passive"))
      (node (ref "RB14") (pin "1") (pinfunction "1_1") (pintype "passive"))
      (node (ref "RB5") (pin "1") (pinfunction "1_1") (pintype "passive"))
      (node (ref "RF5") (pin "1") (pinfunction "1_1") (pintype "passive"))
    )
    (net (code "105") (name "Net-(CT6-2)") (class "Default")
      (node (ref "CT6") (pin "P$2") (pinfunction "2_P$2") (pintype "bidirectional"))
      (node (ref "D8") (pin "K") (pinfunction "C_K") (pintype "passive"))
      (node (ref "RB15") (pin "1") (pinfunction "1_1") (pintype "passive"))
      (node (ref "RB4") (pin "1") (pinfunction "1_1") (pintype "passive"))
      (node (ref "RF4") (pin "1") (pinfunction "1_1") (pintype "passive"))
    )
    (net (code "106") (name "Net-(CT7-2)") (class "Default")
      (node (ref "CT7") (pin "P$2") (pinfunction "2_P$2") (pintype "bidirectional"))
      (node (ref "D7") (pin "K") (pinfunction "C_K") (pintype "passive"))
      (node (ref "RB12") (pin "1") (pinfunction "1_1") (pintype "passive"))
      (node (ref "RB3") (pin "1") (pinfunction "1_1") (pintype "passive"))
      (node (ref "RF3") (pin "1") (pinfunction "1_1") (pintype "passive"))
    )
    (net (code "107") (name "Net-(CT8-2)") (class "Default")
      (node (ref "CT8") (pin "P$2") (pinfunction "2_P$2") (pintype "bidirectional"))
      (node (ref "D6") (pin "K") (pinfunction "C_K") (pintype "passive"))
      (node (ref "RB11") (pin "1") (pinfunction "1_1") (pintype "passive"))
      (node (ref "RB2") (pin "1") (pinfunction "1_1") (pintype "passive"))
      (node (ref "RF2") (pin "1") (pinfunction "1_1") (pintype "passive"))
    )
    (net (code "108") (name "Net-(CT9-2)") (class "Default")
      (node (ref "CT9") (pin "P$2") (pinfunction "2_P$2") (pintype "bidirectional"))
      (node (ref "D5") (pin "K") (pinfunction "C_K") (pintype "passive"))
      (node (ref "RB1") (pin "1") (pinfunction "1_1") (pintype "passive"))
      (node (ref "RB10") (pin "1") (pinfunction "1_1") (pintype "passive"))
      (node (ref "RF1") (pin "1") (pinfunction "1_1") (pintype "passive"))
    )
    (net (code "109") (name "Net-(HSE-2)") (class "Default")
      (node (ref "C29") (pin "1") (pinfunction "1_1") (pintype "passive"))
      (node (ref "HSE") (pin "3") (pinfunction "2_3") (pintype "passive"))
      (node (ref "R21") (pin "2") (pinfunction "2_2") (pintype "passive"))
    )
    (net (code "110") (name "Net-(J$1-SIGNAL)") (class "Default")
      (node (ref "J$1") (pin "SIG") (pinfunction "SIGNAL_SIG") (pintype "bidirectional"))
      (node (ref "RFM69HCW") (pin "8") (pinfunction "ANT_8") (pintype "bidirectional"))
    )
    (net (code "111") (name "Net-(JP1-Pad2)") (class "Default")
      (node (ref "JP1") (pin "2") (pinfunction "2_2") (pintype "passive"))
      (node (ref "R22") (pin "2") (pinfunction "2_2") (pintype "passive"))
    )
    (net (code "112") (name "Net-(LED1-PadA)") (class "Default")
      (node (ref "LED1") (pin "A") (pinfunction "A_A") (pintype "passive"))
      (node (ref "R3") (pin "1") (pinfunction "1_1") (pintype "passive"))
    )
    (net (code "113") (name "Net-(LED2-PadA)") (class "Default")
      (node (ref "LED2") (pin "A") (pinfunction "A_A") (pintype "passive"))
      (node (ref "R4") (pin "1") (pinfunction "1_1") (pintype "passive"))
    )
    (net (code "114") (name "Net-(LED3-PadA)") (class "Default")
      (node (ref "LED3") (pin "A") (pinfunction "A_A") (pintype "passive"))
      (node (ref "R5") (pin "1") (pinfunction "1_1") (pintype "passive"))
    )
    (net (code "115") (name "Net-(LED4-PadA)") (class "Default")
      (node (ref "LED4") (pin "A") (pinfunction "A_A") (pintype "passive"))
      (node (ref "R10") (pin "1") (pinfunction "1_1") (pintype "passive"))
    )
    (net (code "116") (name "Net-(PCB2-GPIO4)") (class "Default")
      (node (ref "J1") (pin "2") (pinfunction "2_2") (pintype "passive"))
      (node (ref "PCB2") (pin "P$47") (pinfunction "GPIO4_P$47") (pintype "bidirectional"))
    )
    (net (code "117") (name "Net-(PCB2-GPIO5)") (class "Default")
      (node (ref "PCB2") (pin "P$69") (pinfunction "GPIO5_P$69") (pintype "bidirectional"))
      (node (ref "SJ28") (pin "2") (pinfunction "2_2") (pintype "passive"))
    )
    (net (code "118") (name "Net-(PCB2-GPIO12)") (class "Default")
      (node (ref "PCB2") (pin "P$72") (pinfunction "GPIO12_P$72") (pintype "bidirectional"))
      (node (ref "SJ8") (pin "1") (pinfunction "1_1") (pintype "passive"))
    )
    (net (code "119") (name "Net-(PCB2-GPIO16)") (class "Default")
      (node (ref "PCB2") (pin "P$76") (pinfunction "GPIO16_P$76") (pintype "bidirectional"))
      (node (ref "SJ29") (pin "1") (pinfunction "1_1") (pintype "passive"))
    )
    (net (code "120") (name "Net-(PCB2-GPIO17)") (class "Default")
      (node (ref "PCB2") (pin "P$51") (pinfunction "GPIO17_P$51") (pintype "bidirectional"))
      (node (ref "SJ32") (pin "2") (pinfunction "2_2") (pintype "passive"))
    )
    (net (code "121") (name "Net-(PCB2-GPIO18)") (class "Default")
      (node (ref "PCB2") (pin "P$52") (pinfunction "GPIO18_P$52") (pintype "bidirectional"))
      (node (ref "SJ31") (pin "1") (pinfunction "1_1") (pintype "passive"))
    )
    (net (code "122") (name "Net-(PCB2-GPIO20)") (class "Default")
      (node (ref "PCB2") (pin "P$78") (pinfunction "GPIO20_P$78") (pintype "bidirectional"))
      (node (ref "SJ30") (pin "1") (pinfunction "1_1") (pintype "passive"))
    )
    (net (code "123") (name "Net-(PCB2-GPIO23)") (class "Default")
      (node (ref "PCB2") (pin "P$56") (pinfunction "GPIO23_P$56") (pintype "bidirectional"))
      (node (ref "SJ33") (pin "1") (pinfunction "1_1") (pintype "passive"))
    )
    (net (code "124") (name "Net-(PCB2-ID_SC*)") (class "Default")
      (node (ref "PCB2") (pin "P$68") (pinfunction "ID_SC*_P$68") (pintype "bidirectional"))
      (node (ref "SJ27") (pin "1") (pinfunction "1_1") (pintype "passive"))
    )
    (net (code "125") (name "Net-(PCB2-ID_SD*)") (class "Default")
      (node (ref "PCB2") (pin "P$67") (pinfunction "ID_SD*_P$67") (pintype "bidirectional"))
      (node (ref "SJ26") (pin "2") (pinfunction "2_2") (pintype "passive"))
    )
    (net (code "126") (name "Net-(Q1-B)") (class "Default")
      (node (ref "Q1") (pin "1") (pinfunction "B_1") (pintype "passive"))
      (node (ref "Q3") (pin "3") (pinfunction "C_3") (pintype "passive"))
      (node (ref "R14") (pin "2") (pinfunction "2_2") (pintype "passive"))
      (node (ref "R9") (pin "1") (pinfunction "1_1") (pintype "passive"))
    )
    (net (code "127") (name "Net-(Q1-C)") (class "Default")
      (node (ref "Q1") (pin "3") (pinfunction "C_3") (pintype "passive"))
      (node (ref "Q2") (pin "1") (pinfunction "B_1") (pintype "passive"))
      (node (ref "R16") (pin "2") (pinfunction "2_2") (pintype "passive"))
    )
    (net (code "128") (name "Net-(Q2-C)") (class "Default")
      (node (ref "Q2") (pin "3") (pinfunction "C_3") (pintype "passive"))
      (node (ref "R11") (pin "1") (pinfunction "1_1") (pintype "passive"))
      (node (ref "R15") (pin "2") (pinfunction "2_2") (pintype "passive"))
      (node (ref "R19") (pin "1") (pinfunction "1_1") (pintype "passive"))
    )
    (net (code "129") (name "Net-(Q3-B)") (class "Default")
      (node (ref "Q3") (pin "1") (pinfunction "B_1") (pintype "passive"))
      (node (ref "R18") (pin "1") (pinfunction "1_1") (pintype "passive"))
    )
    (net (code "130") (name "Net-(Q4-S)") (class "Default")
      (node (ref "Q4") (pin "2") (pinfunction "S_2") (pintype "passive"))
      (node (ref "R8") (pin "1") (pinfunction "1_1") (pintype "passive"))
    )
    (net (code "131") (name "Net-(R41-Pad2)") (class "Default")
      (node (ref "R41") (pin "2") (pinfunction "2_2") (pintype "passive"))
      (node (ref "R51") (pin "1") (pinfunction "1_1") (pintype "passive"))
      (node (ref "RV3") (pin "1") (pinfunction "1_1") (pintype "passive"))
    )
    (net (code "132") (name "Net-(R42-Pad1)") (class "Default")
      (node (ref "R42") (pin "1") (pinfunction "1_1") (pintype "passive"))
      (node (ref "R52") (pin "1") (pinfunction "1_1") (pintype "passive"))
      (node (ref "RV2") (pin "1") (pinfunction "1_1") (pintype "passive"))
    )
    (net (code "133") (name "Net-(R43-Pad1)") (class "Default")
      (node (ref "R43") (pin "1") (pinfunction "1_1") (pintype "passive"))
      (node (ref "R53") (pin "1") (pinfunction "1_1") (pintype "passive"))
      (node (ref "RV1") (pin "1") (pinfunction "1_1") (pintype "passive"))
    )
    (net (code "134") (name "Net-(RB16-Pad2)") (class "Default")
      (node (ref "RB16") (pin "2") (pinfunction "2_2") (pintype "passive"))
      (node (ref "RB7") (pin "2") (pinfunction "2_2") (pintype "passive"))
      (node (ref "S33") (pin "1") (pinfunction "1_1") (pintype "passive"))
    )
    (net (code "135") (name "Net-(RB17-Pad2)") (class "Default")
      (node (ref "RB17") (pin "2") (pinfunction "2_2") (pintype "passive"))
      (node (ref "RB8") (pin "2") (pinfunction "2_2") (pintype "passive"))
      (node (ref "S22") (pin "1") (pinfunction "1_1") (pintype "passive"))
    )
    (net (code "136") (name "Net-(RB18-Pad2)") (class "Default")
      (node (ref "RB18") (pin "2") (pinfunction "2_2") (pintype "passive"))
      (node (ref "RB9") (pin "2") (pinfunction "2_2") (pintype "passive"))
      (node (ref "S11") (pin "1") (pinfunction "1_1") (pintype "passive"))
    )
    (net (code "137") (name "Net-(SJ1-Pad1)") (class "Default")
      (node (ref "SJ1") (pin "1") (pinfunction "1_1") (pintype "passive"))
      (node (ref "SV1") (pin "2") (pinfunction "2_2") (pintype "passive"))
    )
    (net (code "138") (name "Net-(U1-3V3)") (class "Default")
      (node (ref "SJ23") (pin "1") (pinfunction "1_1") (pintype "passive"))
      (node (ref "U1") (pin "2") (pinfunction "3V3_2") (pintype "power_in"))
    )
    (net (code "139") (name "Net-(U1-EN)") (class "Default")
      (node (ref "C16") (pin "2") (pinfunction "2_2") (pintype "passive"))
      (node (ref "U1") (pin "3") (pinfunction "EN_3") (pintype "input"))
    )
    (net (code "140") (name "Net-(U1-IO0)") (class "Default")
      (node (ref "BOOT_ESP") (pin "2") (pinfunction "2_2") (pintype "passive"))
      (node (ref "U1") (pin "25") (pinfunction "IO0_25") (pintype "bidirectional"))
    )
    (net (code "141") (name "Net-(U1-IO17)") (class "Default")
      (node (ref "SJ24") (pin "1") (pinfunction "1_1") (pintype "passive"))
      (node (ref "U1") (pin "28") (pinfunction "IO17_28") (pintype "bidirectional"))
    )
    (net (code "142") (name "Net-(U1-IO18)") (class "Default")
      (node (ref "SJ25") (pin "1") (pinfunction "1_1") (pintype "passive"))
      (node (ref "U1") (pin "30") (pinfunction "IO18_30") (pintype "bidirectional"))
    )
    (net (code "143") (name "Net-(VT1-TIP)") (class "Default")
      (node (ref "R43") (pin "2") (pinfunction "2_2") (pintype "passive"))
      (node (ref "VT1") (pin "PWR2") (pinfunction "TIP_PWR2") (pintype "bidirectional"))
    )
    (net (code "144") (name "Net-(VT2-TIP)") (class "Default")
      (node (ref "R42") (pin "2") (pinfunction "2_2") (pintype "passive"))
      (node (ref "VT2") (pin "PWR2") (pinfunction "TIP_PWR2") (pintype "bidirectional"))
    )
    (net (code "145") (name "Net-(VT3-TIP)") (class "Default")
      (node (ref "R41") (pin "1") (pinfunction "1_1") (pintype "passive"))
      (node (ref "VT3") (pin "PWR2") (pinfunction "TIP_PWR2") (pintype "bidirectional"))
    )
    (net (code "146") (name "unconnected-(CT1-3-PadP$3)") (class "Default")
      (node (ref "CT1") (pin "P$3") (pinfunction "3_P$3") (pintype "bidirectional"))
    )
    (net (code "147") (name "unconnected-(CT2-3-PadP$3)") (class "Default")
      (node (ref "CT2") (pin "P$3") (pinfunction "3_P$3") (pintype "bidirectional"))
    )
    (net (code "148") (name "unconnected-(CT3-3-PadP$3)") (class "Default")
      (node (ref "CT3") (pin "P$3") (pinfunction "3_P$3") (pintype "bidirectional"))
    )
    (net (code "149") (name "unconnected-(CT4-3-PadP$3)") (class "Default")
      (node (ref "CT4") (pin "P$3") (pinfunction "3_P$3") (pintype "bidirectional"))
    )
    (net (code "150") (name "unconnected-(CT5-3-PadP$3)") (class "Default")
      (node (ref "CT5") (pin "P$3") (pinfunction "3_P$3") (pintype "bidirectional"))
    )
    (net (code "151") (name "unconnected-(CT6-3-PadP$3)") (class "Default")
      (node (ref "CT6") (pin "P$3") (pinfunction "3_P$3") (pintype "bidirectional"))
    )
    (net (code "152") (name "unconnected-(CT7-3-PadP$3)") (class "Default")
      (node (ref "CT7") (pin "P$3") (pinfunction "3_P$3") (pintype "bidirectional"))
    )
    (net (code "153") (name "unconnected-(CT8-3-PadP$3)") (class "Default")
      (node (ref "CT8") (pin "P$3") (pinfunction "3_P$3") (pintype "bidirectional"))
    )
    (net (code "154") (name "unconnected-(CT9-3-PadP$3)") (class "Default")
      (node (ref "CT9") (pin "P$3") (pinfunction "3_P$3") (pintype "bidirectional"))
    )
    (net (code "155") (name "unconnected-(PCB2-3V3-PadP$41)") (class "Default")
      (node (ref "PCB2") (pin "P$41") (pinfunction "3V3_P$41") (pintype "bidirectional"))
    )
    (net (code "156") (name "unconnected-(PCB2-3V3-PadP$57)") (class "Default")
      (node (ref "PCB2") (pin "P$57") (pinfunction "3V3_P$57") (pintype "bidirectional"))
    )
    (net (code "157") (name "unconnected-(PCB2-GPIO2-PadP$43)") (class "Default")
      (node (ref "PCB2") (pin "P$43") (pinfunction "GPIO2_P$43") (pintype "bidirectional"))
    )
    (net (code "158") (name "unconnected-(PCB2-GPIO3-PadP$45)") (class "Default")
      (node (ref "PCB2") (pin "P$45") (pinfunction "GPIO3_P$45") (pintype "bidirectional"))
    )
    (net (code "159") (name "unconnected-(PCB2-GPIO6-PadP$71)") (class "Default")
      (node (ref "PCB2") (pin "P$71") (pinfunction "GPIO6_P$71") (pintype "bidirectional"))
    )
    (net (code "160") (name "unconnected-(PCB2-GPIO7-PadP$66)") (class "Default")
      (node (ref "PCB2") (pin "P$66") (pinfunction "GPIO7_P$66") (pintype "bidirectional"))
    )
    (net (code "161") (name "unconnected-(PCB2-GPIO13-PadP$73)") (class "Default")
      (node (ref "PCB2") (pin "P$73") (pinfunction "GPIO13_P$73") (pintype "bidirectional"))
    )
    (net (code "162") (name "unconnected-(PCB2-GPIO19-PadP$75)") (class "Default")
      (node (ref "PCB2") (pin "P$75") (pinfunction "GPIO19_P$75") (pintype "bidirectional"))
    )
    (net (code "163") (name "unconnected-(PCB2-GPIO21-PadP$80)") (class "Default")
      (node (ref "PCB2") (pin "P$80") (pinfunction "GPIO21_P$80") (pintype "bidirectional"))
    )
    (net (code "164") (name "unconnected-(PCB2-GPIO22-PadP$55)") (class "Default")
      (node (ref "PCB2") (pin "P$55") (pinfunction "GPIO22_P$55") (pintype "bidirectional"))
    )
    (net (code "165") (name "unconnected-(PCB2-GPIO25-PadP$62)") (class "Default")
      (node (ref "PCB2") (pin "P$62") (pinfunction "GPIO25_P$62") (pintype "bidirectional"))
    )
    (net (code "166") (name "unconnected-(PCB2-GPIO26-PadP$77)") (class "Default")
      (node (ref "PCB2") (pin "P$77") (pinfunction "GPIO26_P$77") (pintype "bidirectional"))
    )
    (net (code "167") (name "unconnected-(RFM69HCW-CLK-Pad5)") (class "Default")
      (node (ref "RFM69HCW") (pin "5") (pinfunction "CLK_5") (pintype "output"))
    )
    (net (code "168") (name "unconnected-(RFM69HCW-DCLK{slash}CFIL{slash}FFIT-Pad4)") (class "Default")
      (node (ref "RFM69HCW") (pin "4") (pinfunction "DCLK/CFIL/FFIT_4") (pintype "bidirectional"))
    )
    (net (code "169") (name "unconnected-(RFM69HCW-FSK{slash}DATA{slash}NFFS-Pad3)") (class "Default")
      (node (ref "RFM69HCW") (pin "3") (pinfunction "FSK/DATA/NFFS_3") (pintype "bidirectional"))
    )
    (net (code "170") (name "unconnected-(RFM69HCW-~{INT}-Pad11)") (class "Default")
      (node (ref "RFM69HCW") (pin "11") (pinfunction "~{INT}_11") (pintype "bidirectional"))
    )
    (net (code "171") (name "unconnected-(STM32F303VE-PB2-Pad37)") (class "Default")
      (node (ref "STM32F303VE") (pin "37") (pinfunction "PB2_37") (pintype "bidirectional"))
    )
    (net (code "172") (name "unconnected-(STM32F303VE-PB4-Pad90)") (class "Default")
      (node (ref "STM32F303VE") (pin "90") (pinfunction "PB4_90") (pintype "bidirectional"))
    )
    (net (code "173") (name "unconnected-(STM32F303VE-PB13-Pad52)") (class "Default")
      (node (ref "STM32F303VE") (pin "52") (pinfunction "PB13_52") (pintype "bidirectional"))
    )
    (net (code "174") (name "unconnected-(STM32F303VE-PC5-Pad34)") (class "Default")
      (node (ref "STM32F303VE") (pin "34") (pinfunction "PC5_34") (pintype "bidirectional"))
    )
    (net (code "175") (name "unconnected-(STM32F303VE-PC13-Pad7)") (class "Default")
      (node (ref "STM32F303VE") (pin "7") (pinfunction "PC13_7") (pintype "bidirectional"))
    )
    (net (code "176") (name "unconnected-(STM32F303VE-PD1-Pad82)") (class "Default")
      (node (ref "STM32F303VE") (pin "82") (pinfunction "PD1_82") (pintype "bidirectional"))
    )
    (net (code "177") (name "unconnected-(STM32F303VE-PD2-Pad83)") (class "Default")
      (node (ref "STM32F303VE") (pin "83") (pinfunction "PD2_83") (pintype "bidirectional"))
    )
    (net (code "178") (name "unconnected-(STM32F303VE-PD4-Pad85)") (class "Default")
      (node (ref "STM32F303VE") (pin "85") (pinfunction "PD4_85") (pintype "bidirectional"))
    )
    (net (code "179") (name "unconnected-(STM32F303VE-PD6-Pad87)") (class "Default")
      (node (ref "STM32F303VE") (pin "87") (pinfunction "PD6_87") (pintype "bidirectional"))
    )
    (net (code "180") (name "unconnected-(STM32F303VE-PD7-Pad88)") (class "Default")
      (node (ref "STM32F303VE") (pin "88") (pinfunction "PD7_88") (pintype "bidirectional"))
    )
    (net (code "181") (name "unconnected-(STM32F303VE-PD14-Pad61)") (class "Default")
      (node (ref "STM32F303VE") (pin "61") (pinfunction "PD14_61") (pintype "bidirectional"))
    )
    (net (code "182") (name "unconnected-(STM32F303VE-PD15-Pad62)") (class "Default")
      (node (ref "STM32F303VE") (pin "62") (pinfunction "PD15_62") (pintype "bidirectional"))
    )
    (net (code "183") (name "unconnected-(STM32F303VE-PE14-Pad45)") (class "Default")
      (node (ref "STM32F303VE") (pin "45") (pinfunction "PE14_45") (pintype "bidirectional"))
    )
    (net (code "184") (name "unconnected-(STM32F303VE-PE15-Pad46)") (class "Default")
      (node (ref "STM32F303VE") (pin "46") (pinfunction "PE15_46") (pintype "bidirectional"))
    )
    (net (code "185") (name "unconnected-(STM32F303VE-PF6-Pad73)") (class "Default")
      (node (ref "STM32F303VE") (pin "73") (pinfunction "PF6_73") (pintype "bidirectional"))
    )
    (net (code "186") (name "unconnected-(STM32F303VE-PF9-Pad10)") (class "Default")
      (node (ref "STM32F303VE") (pin "10") (pinfunction "PF9_10") (pintype "bidirectional"))
    )
    (net (code "187") (name "unconnected-(STM32F303VE-PF10-Pad11)") (class "Default")
      (node (ref "STM32F303VE") (pin "11") (pinfunction "PF10_11") (pintype "bidirectional"))
    )
    (net (code "188") (name "unconnected-(SV2-Pad2)") (class "Default")
      (node (ref "SV2") (pin "2") (pinfunction "2_2") (pintype "passive"))
    )
    (net (code "189") (name "unconnected-(U1-IO4-Pad26)") (class "Default")
      (node (ref "U1") (pin "26") (pinfunction "IO4_26") (pintype "bidirectional"))
    )
    (net (code "190") (name "unconnected-(U1-IO5-Pad29)") (class "Default")
      (node (ref "U1") (pin "29") (pinfunction "IO5_29") (pintype "bidirectional"))
    )
    (net (code "191") (name "unconnected-(U1-IO23-Pad37)") (class "Default")
      (node (ref "U1") (pin "37") (pinfunction "IO23_37") (pintype "bidirectional"))
    )
    (net (code "192") (name "unconnected-(U1-IO25-Pad10)") (class "Default")
      (node (ref "U1") (pin "10") (pinfunction "IO25_10") (pintype "bidirectional"))
    )
    (net (code "193") (name "unconnected-(U1-IO26-Pad11)") (class "Default")
      (node (ref "U1") (pin "11") (pinfunction "IO26_11") (pintype "bidirectional"))
    )
    (net (code "194") (name "unconnected-(U1-IO27-Pad12)") (class "Default")
      (node (ref "U1") (pin "12") (pinfunction "IO27_12") (pintype "bidirectional"))
    )
    (net (code "195") (name "unconnected-(U1-IO32-Pad8)") (class "Default")
      (node (ref "U1") (pin "8") (pinfunction "IO32_8") (pintype "bidirectional"))
    )
    (net (code "196") (name "unconnected-(U1-IO33-Pad9)") (class "Default")
      (node (ref "U1") (pin "9") (pinfunction "IO33_9") (pintype "bidirectional"))
    )
    (net (code "197") (name "unconnected-(U1-IO34-Pad6)") (class "Default")
      (node (ref "U1") (pin "6") (pinfunction "IO34_6") (pintype "bidirectional"))
    )
    (net (code "198") (name "unconnected-(U1-IO35-Pad7)") (class "Default")
      (node (ref "U1") (pin "7") (pinfunction "IO35_7") (pintype "bidirectional"))
    )
    (net (code "199") (name "unconnected-(U1-SCL{slash}CLK-Pad20)") (class "Default")
      (node (ref "U1") (pin "20") (pinfunction "SCL/CLK_20") (pintype "bidirectional"))
    )
    (net (code "200") (name "unconnected-(U1-SCS{slash}CMD-Pad19)") (class "Default")
      (node (ref "U1") (pin "19") (pinfunction "SCS/CMD_19") (pintype "bidirectional"))
    )
    (net (code "201") (name "unconnected-(U1-SDI{slash}SD1-Pad22)") (class "Default")
      (node (ref "U1") (pin "22") (pinfunction "SDI/SD1_22") (pintype "bidirectional"))
    )
    (net (code "202") (name "unconnected-(U1-SDO{slash}SD0-Pad21)") (class "Default")
      (node (ref "U1") (pin "21") (pinfunction "SDO/SD0_21") (pintype "bidirectional"))
    )
    (net (code "203") (name "unconnected-(U1-SENSOR_VN-Pad5)") (class "Default")
      (node (ref "U1") (pin "5") (pinfunction "SENSOR_VN_5") (pintype "input"))
    )
    (net (code "204") (name "unconnected-(U1-SENSOR_VP-Pad4)") (class "Default")
      (node (ref "U1") (pin "4") (pinfunction "SENSOR_VP_4") (pintype "input"))
    )
    (net (code "205") (name "unconnected-(U1-SHD{slash}SD2-Pad17)") (class "Default")
      (node (ref "U1") (pin "17") (pinfunction "SHD/SD2_17") (pintype "bidirectional"))
    )
    (net (code "206") (name "unconnected-(U1-SWP{slash}SD3-Pad18)") (class "Default")
      (node (ref "U1") (pin "18") (pinfunction "SWP/SD3_18") (pintype "bidirectional"))
    )
  )
)
